# BattleBitsManual.net
KiCad netlist of a schematic drawn in EAGLE
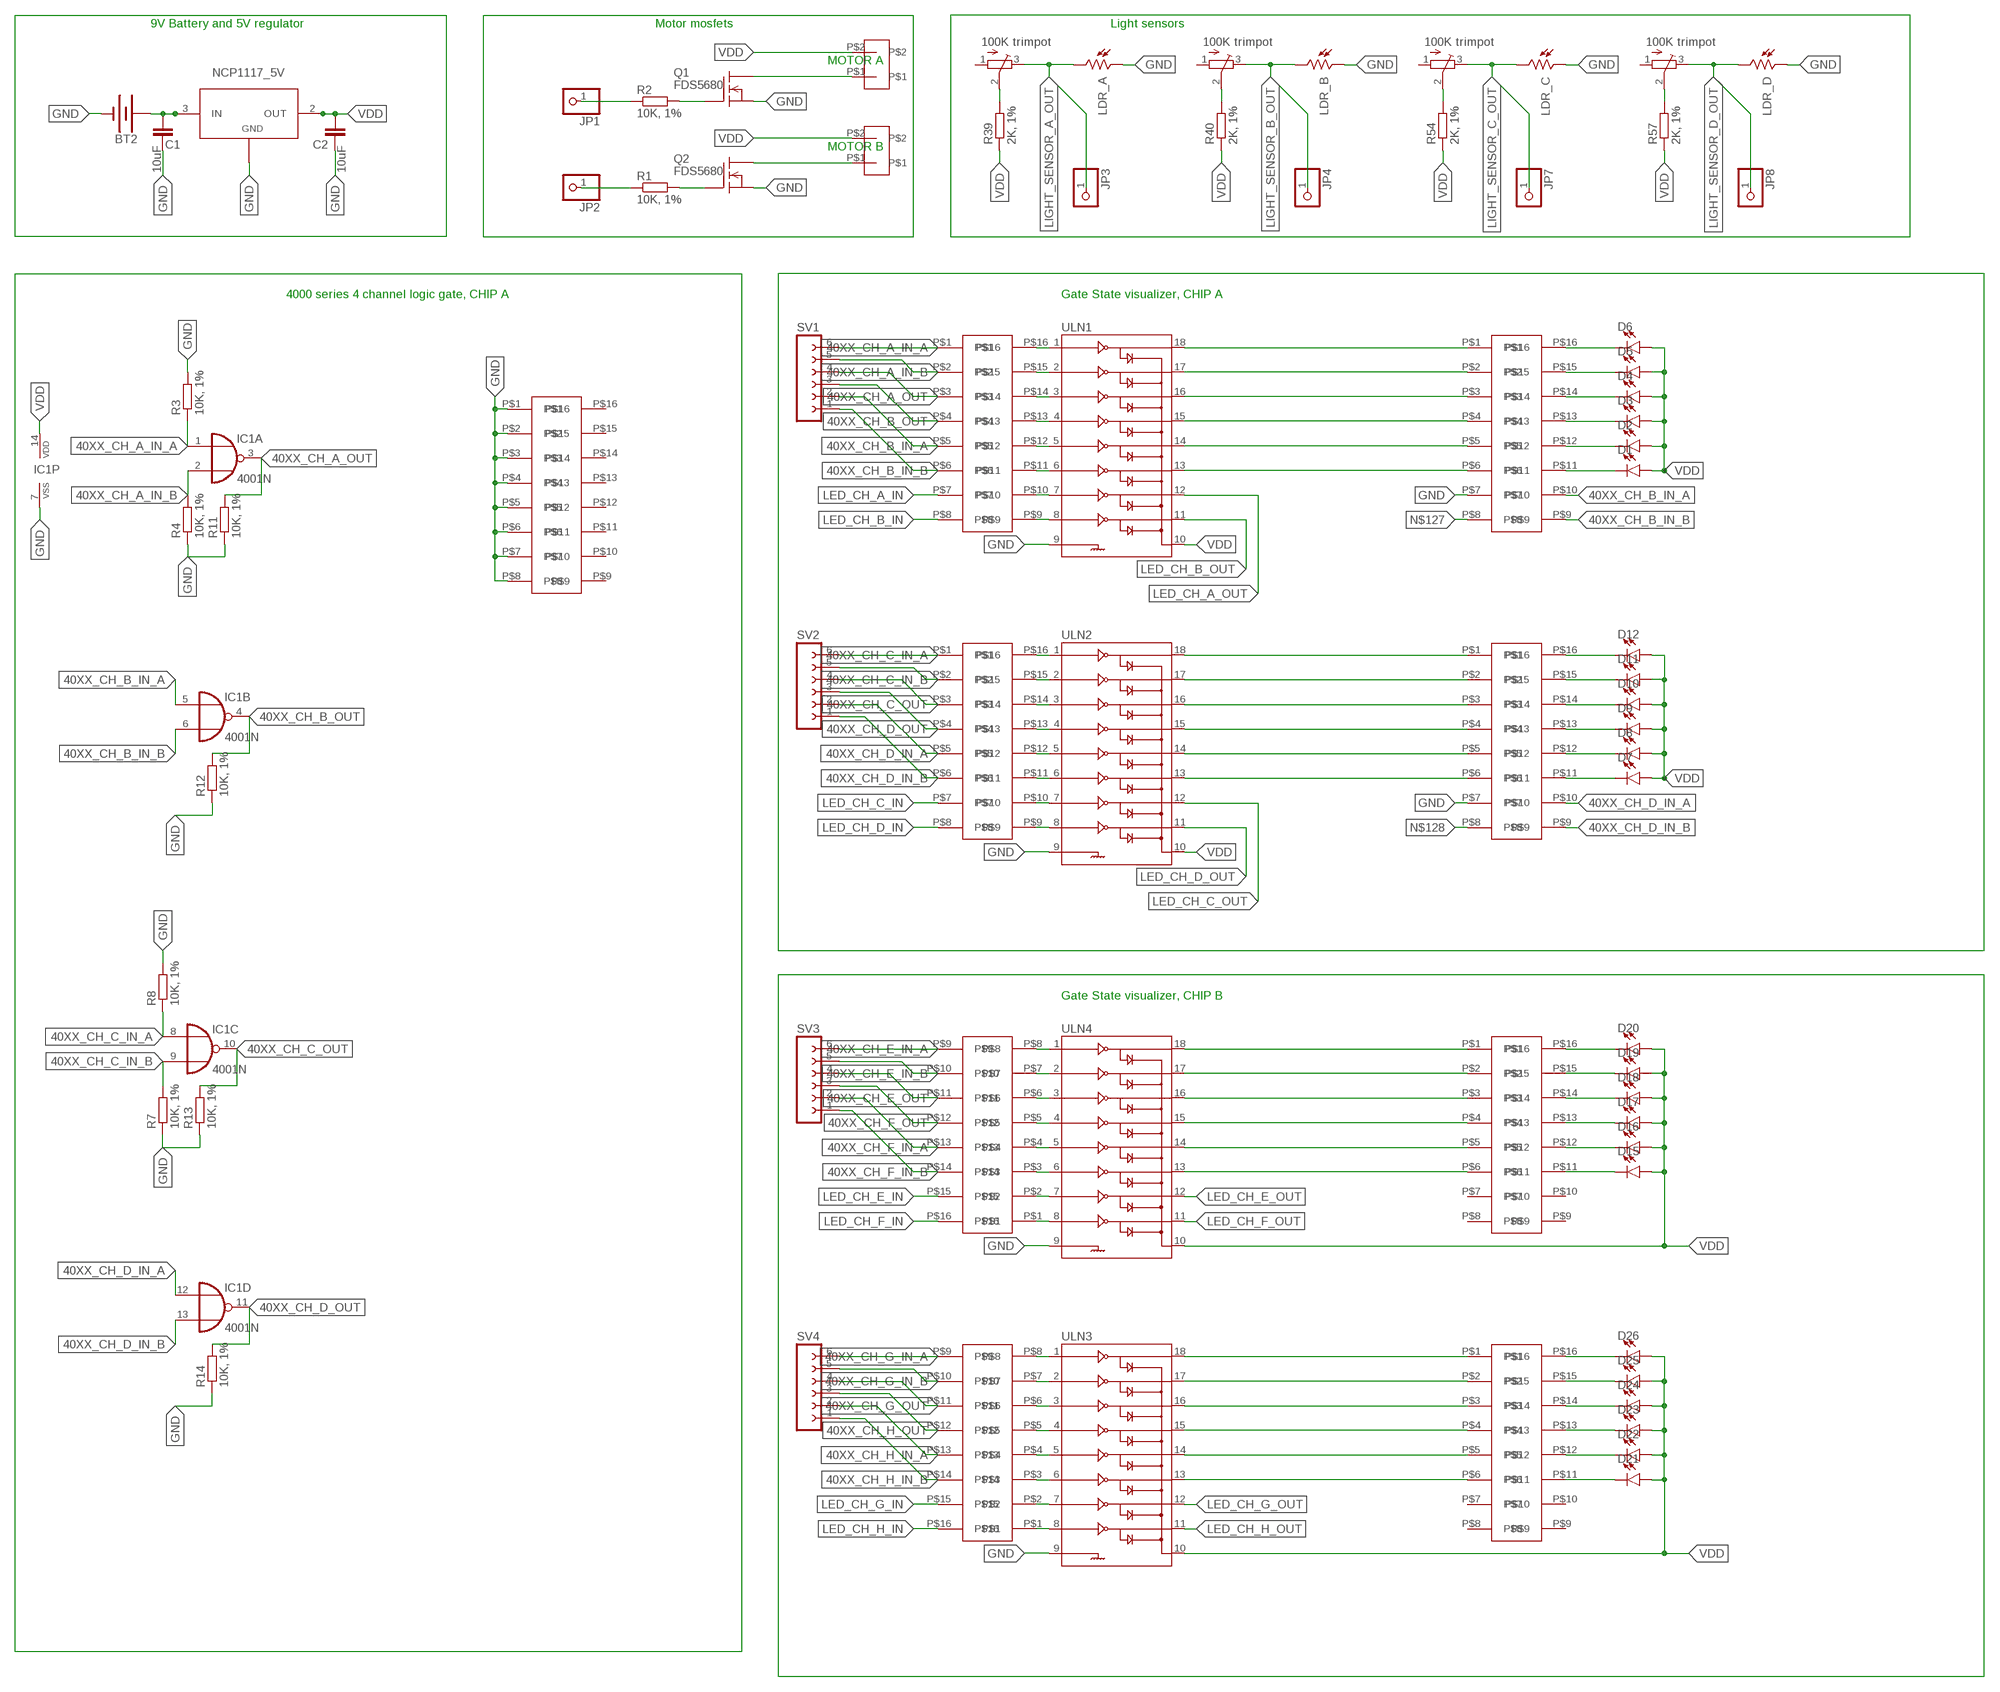
[diagram p0: schematic, sheet 1, part 1 of 3]
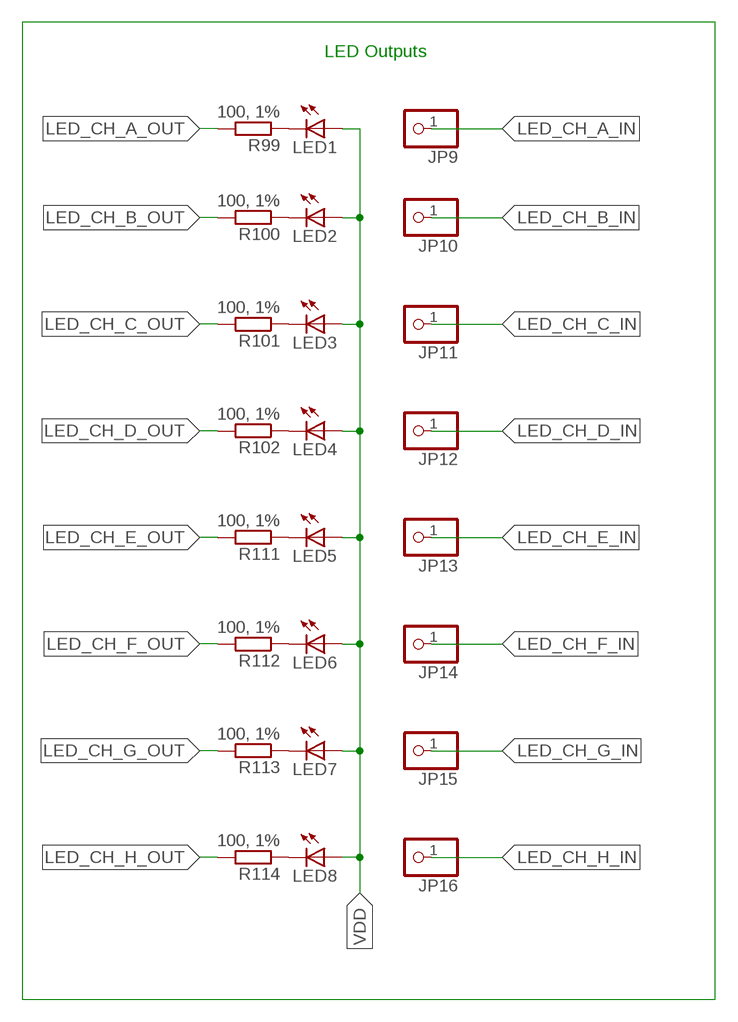
[diagram p1: schematic, sheet 1, part 2 of 3]
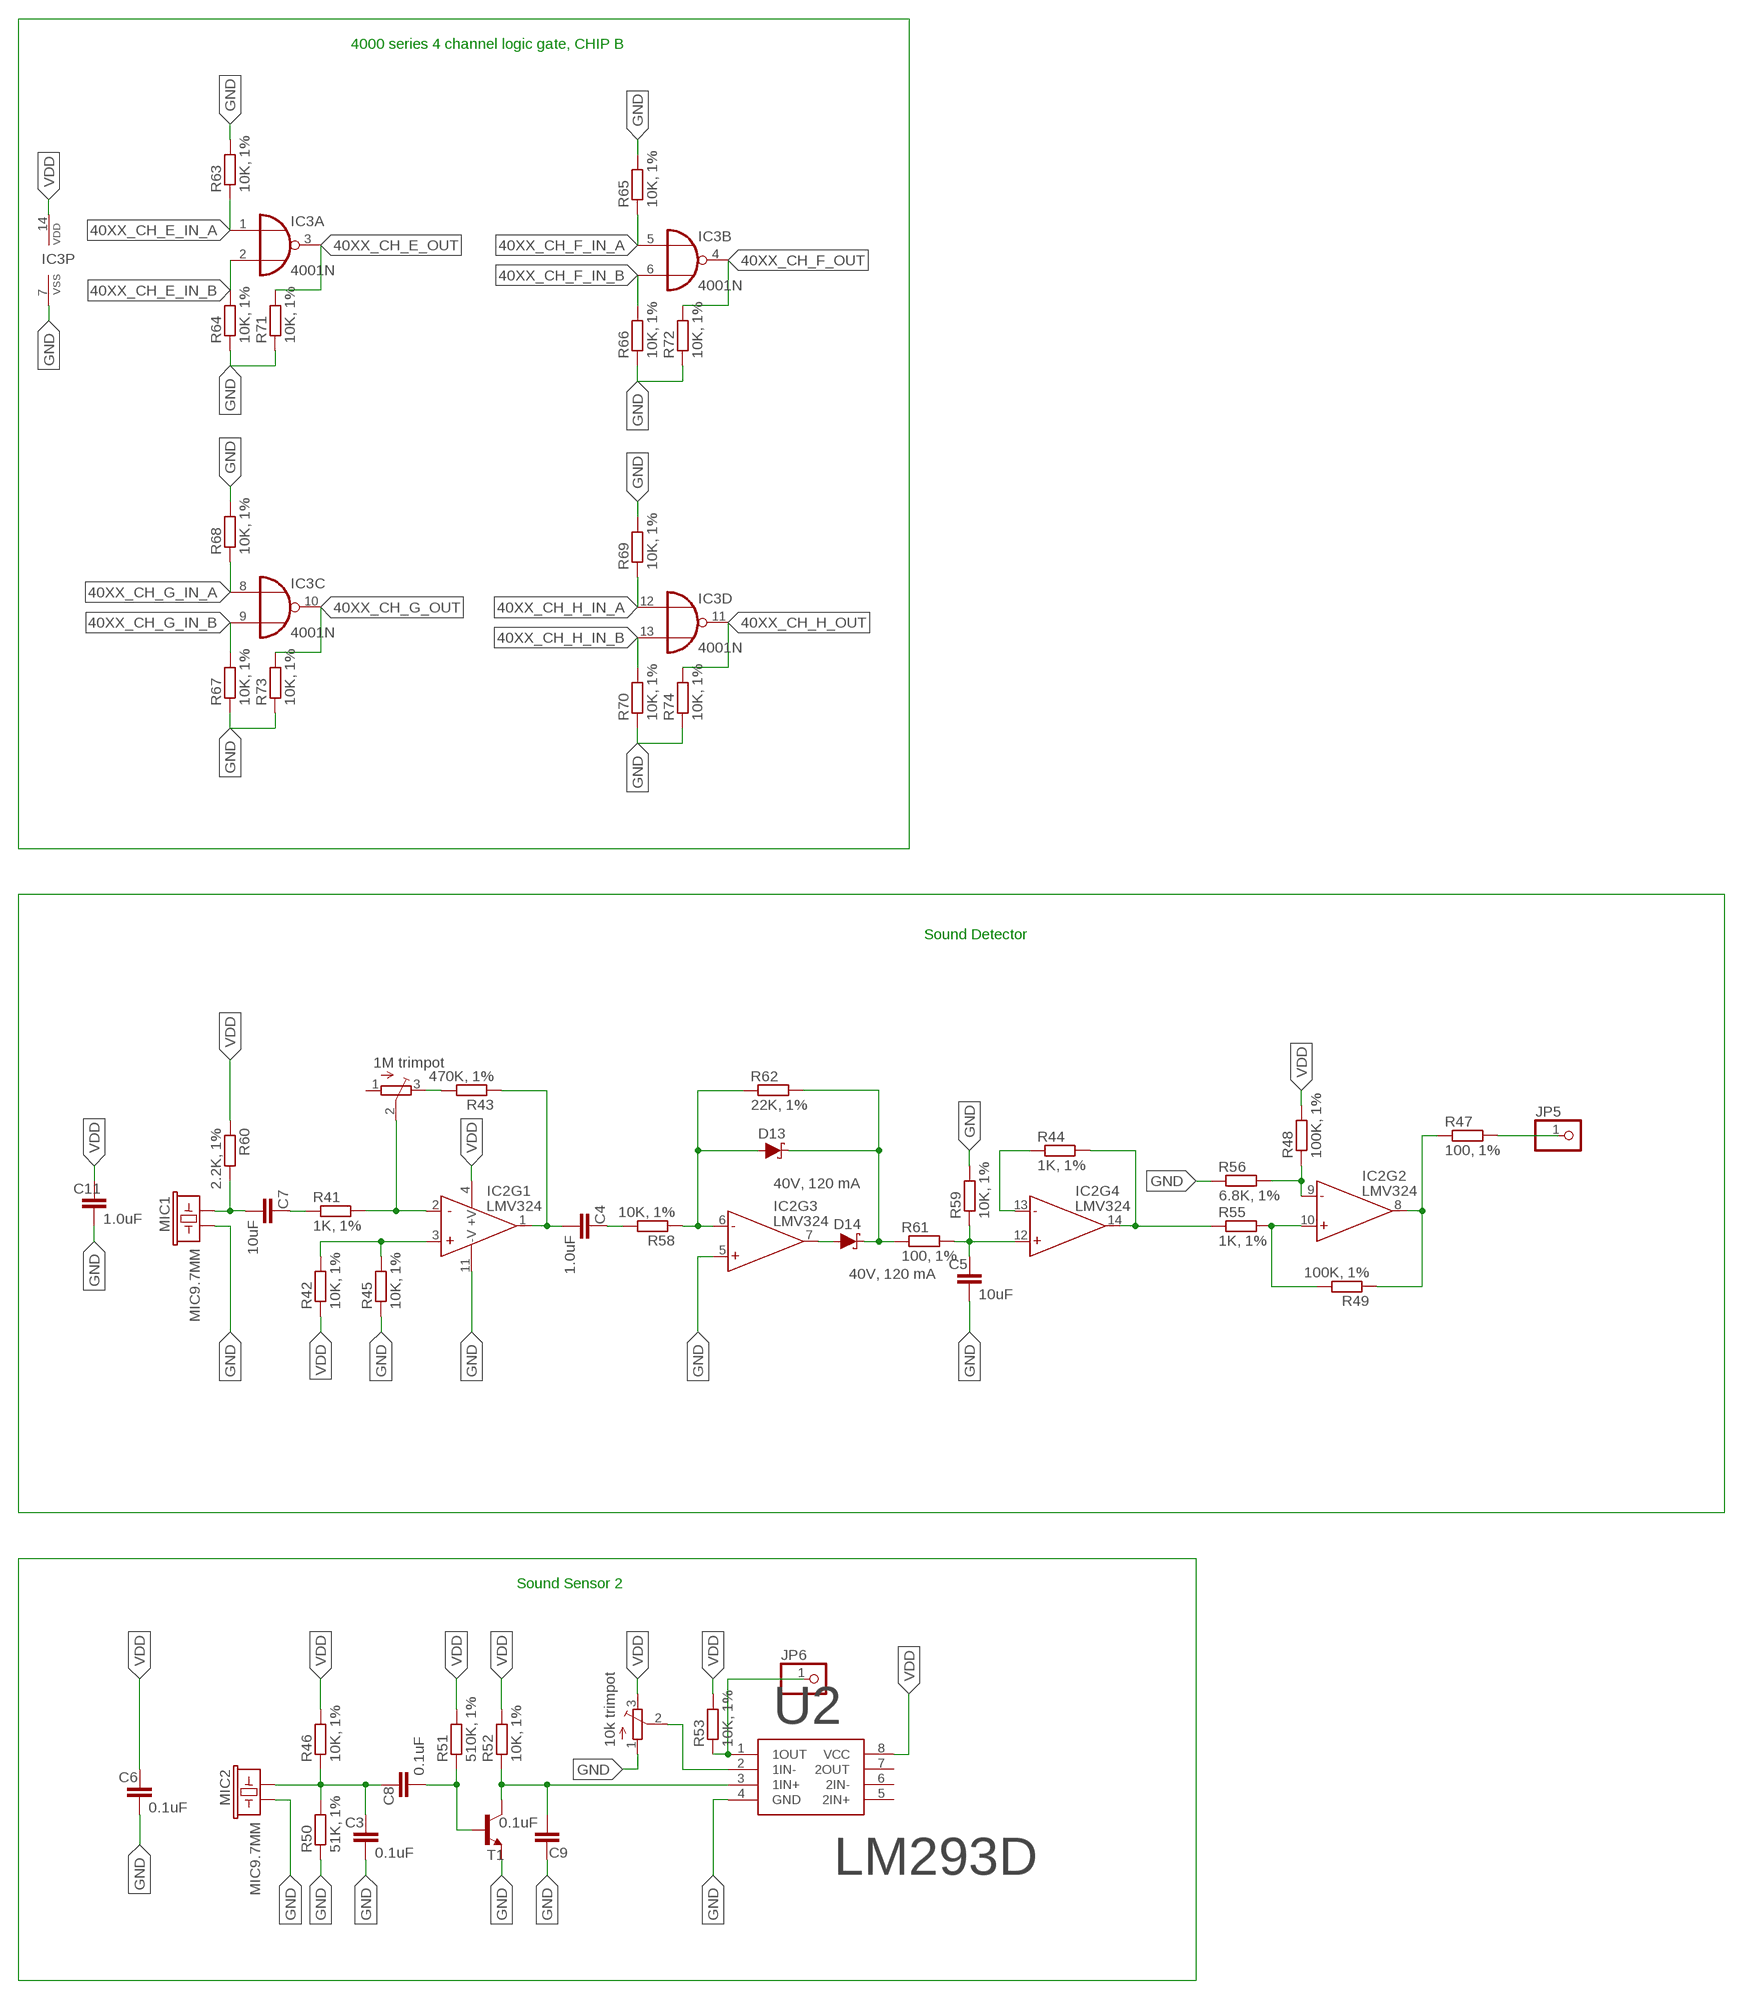
[diagram p2: schematic, sheet 1, part 3 of 3]

(export (version "E")
  (design (tool "Eeschema 10.0.6"))
  (components
    (comp (ref "BT2")
      (value "BATTERY-9V")
      (footprint "eagle-import:BATTCON_9V")
      (libsource (lib "eagle-import") (part "BATTERY-9V"))
    )
    (comp (ref "C1")
      (value "10uF")
      (footprint "eagle-import:C3216")
      (libsource (lib "eagle-import") (part "C-EUC3216"))
    )
    (comp (ref "C2")
      (value "10uF")
      (footprint "eagle-import:C3216")
      (libsource (lib "eagle-import") (part "C-EUC3216"))
    )
    (comp (ref "C3")
      (value "0.1uF")
      (footprint "eagle-import:C3216")
      (libsource (lib "eagle-import") (part "C-EUC3216"))
    )
    (comp (ref "C4")
      (value "1.0uF")
      (footprint "eagle-import:C3216")
      (libsource (lib "eagle-import") (part "C-EUC3216"))
    )
    (comp (ref "C5")
      (value "10uF")
      (footprint "eagle-import:C3216")
      (libsource (lib "eagle-import") (part "C-EUC3216"))
    )
    (comp (ref "C6")
      (value "0.1uF")
      (footprint "eagle-import:C3216")
      (libsource (lib "eagle-import") (part "C-EUC3216"))
    )
    (comp (ref "C7")
      (value "10uF")
      (footprint "eagle-import:C3216")
      (libsource (lib "eagle-import") (part "C-EUC3216"))
    )
    (comp (ref "C8")
      (value "0.1uF")
      (footprint "eagle-import:C3216")
      (libsource (lib "eagle-import") (part "C-EUC3216"))
    )
    (comp (ref "C9")
      (value "0.1uF")
      (footprint "eagle-import:C3216")
      (libsource (lib "eagle-import") (part "C-EUC3216"))
    )
    (comp (ref "C11")
      (value "1.0uF")
      (footprint "eagle-import:C3216")
      (libsource (lib "eagle-import") (part "C-EUC3216"))
    )
    (comp (ref "D1")
      (value "LED1206")
      (footprint "eagle-import:LED-1206")
      (libsource (lib "eagle-import") (part "LED1206"))
    )
    (comp (ref "D2")
      (value "LED1206")
      (footprint "eagle-import:LED-1206")
      (libsource (lib "eagle-import") (part "LED1206"))
    )
    (comp (ref "D3")
      (value "LED1206")
      (footprint "eagle-import:LED-1206")
      (libsource (lib "eagle-import") (part "LED1206"))
    )
    (comp (ref "D4")
      (value "LED1206")
      (footprint "eagle-import:LED-1206")
      (libsource (lib "eagle-import") (part "LED1206"))
    )
    (comp (ref "D5")
      (value "LED1206")
      (footprint "eagle-import:LED-1206")
      (libsource (lib "eagle-import") (part "LED1206"))
    )
    (comp (ref "D6")
      (value "LED1206")
      (footprint "eagle-import:LED-1206")
      (libsource (lib "eagle-import") (part "LED1206"))
    )
    (comp (ref "D7")
      (value "LED1206")
      (footprint "eagle-import:LED-1206")
      (libsource (lib "eagle-import") (part "LED1206"))
    )
    (comp (ref "D8")
      (value "LED1206")
      (footprint "eagle-import:LED-1206")
      (libsource (lib "eagle-import") (part "LED1206"))
    )
    (comp (ref "D9")
      (value "LED1206")
      (footprint "eagle-import:LED-1206")
      (libsource (lib "eagle-import") (part "LED1206"))
    )
    (comp (ref "D10")
      (value "LED1206")
      (footprint "eagle-import:LED-1206")
      (libsource (lib "eagle-import") (part "LED1206"))
    )
    (comp (ref "D11")
      (value "LED1206")
      (footprint "eagle-import:LED-1206")
      (libsource (lib "eagle-import") (part "LED1206"))
    )
    (comp (ref "D12")
      (value "LED1206")
      (footprint "eagle-import:LED-1206")
      (libsource (lib "eagle-import") (part "LED1206"))
    )
    (comp (ref "D13")
      (value "40V, 120 mA")
      (footprint "eagle-import:SOT23-3")
      (libsource (lib "eagle-import") (part "DIODE-SCHOTTKY-ZLLS500"))
    )
    (comp (ref "D14")
      (value "40V, 120 mA")
      (footprint "eagle-import:SOT23-3")
      (libsource (lib "eagle-import") (part "DIODE-SCHOTTKY-ZLLS500"))
    )
    (comp (ref "D15")
      (value "LED1206")
      (footprint "eagle-import:LED-1206")
      (libsource (lib "eagle-import") (part "LED1206"))
    )
    (comp (ref "D16")
      (value "LED1206")
      (footprint "eagle-import:LED-1206")
      (libsource (lib "eagle-import") (part "LED1206"))
    )
    (comp (ref "D17")
      (value "LED1206")
      (footprint "eagle-import:LED-1206")
      (libsource (lib "eagle-import") (part "LED1206"))
    )
    (comp (ref "D18")
      (value "LED1206")
      (footprint "eagle-import:LED-1206")
      (libsource (lib "eagle-import") (part "LED1206"))
    )
    (comp (ref "D19")
      (value "LED1206")
      (footprint "eagle-import:LED-1206")
      (libsource (lib "eagle-import") (part "LED1206"))
    )
    (comp (ref "D20")
      (value "LED1206")
      (footprint "eagle-import:LED-1206")
      (libsource (lib "eagle-import") (part "LED1206"))
    )
    (comp (ref "D21")
      (value "LED1206")
      (footprint "eagle-import:LED-1206")
      (libsource (lib "eagle-import") (part "LED1206"))
    )
    (comp (ref "D22")
      (value "LED1206")
      (footprint "eagle-import:LED-1206")
      (libsource (lib "eagle-import") (part "LED1206"))
    )
    (comp (ref "D23")
      (value "LED1206")
      (footprint "eagle-import:LED-1206")
      (libsource (lib "eagle-import") (part "LED1206"))
    )
    (comp (ref "D24")
      (value "LED1206")
      (footprint "eagle-import:LED-1206")
      (libsource (lib "eagle-import") (part "LED1206"))
    )
    (comp (ref "D25")
      (value "LED1206")
      (footprint "eagle-import:LED-1206")
      (libsource (lib "eagle-import") (part "LED1206"))
    )
    (comp (ref "D26")
      (value "LED1206")
      (footprint "eagle-import:LED-1206")
      (libsource (lib "eagle-import") (part "LED1206"))
    )
    (comp (ref "IC1")
      (value "4001N")
      (footprint "eagle-import:DIL14")
      (libsource (lib "eagle-import") (part "4001N"))
    )
    (comp (ref "IC2")
      (value "LMV324")
      (footprint "eagle-import:SO014")
      (libsource (lib "eagle-import") (part "LMV324"))
    )
    (comp (ref "IC3")
      (value "4001N")
      (footprint "eagle-import:DIL14")
      (libsource (lib "eagle-import") (part "4001N"))
    )
    (comp (ref "JP1")
      (value "PINHD-1X1")
      (footprint "eagle-import:1X01")
      (libsource (lib "eagle-import") (part "PINHD-1X1"))
    )
    (comp (ref "JP2")
      (value "PINHD-1X1")
      (footprint "eagle-import:1X01")
      (libsource (lib "eagle-import") (part "PINHD-1X1"))
    )
    (comp (ref "JP3")
      (value "PINHD-1X1")
      (footprint "eagle-import:1X01")
      (libsource (lib "eagle-import") (part "PINHD-1X1"))
    )
    (comp (ref "JP4")
      (value "PINHD-1X1")
      (footprint "eagle-import:1X01")
      (libsource (lib "eagle-import") (part "PINHD-1X1"))
    )
    (comp (ref "JP5")
      (value "PINHD-1X1")
      (footprint "eagle-import:1X01")
      (libsource (lib "eagle-import") (part "PINHD-1X1"))
    )
    (comp (ref "JP6")
      (value "PINHD-1X1")
      (footprint "eagle-import:1X01")
      (libsource (lib "eagle-import") (part "PINHD-1X1"))
    )
    (comp (ref "JP7")
      (value "PINHD-1X1")
      (footprint "eagle-import:1X01")
      (libsource (lib "eagle-import") (part "PINHD-1X1"))
    )
    (comp (ref "JP8")
      (value "PINHD-1X1")
      (footprint "eagle-import:1X01")
      (libsource (lib "eagle-import") (part "PINHD-1X1"))
    )
    (comp (ref "JP9")
      (value "PINHD-1X1")
      (footprint "eagle-import:1X01")
      (libsource (lib "eagle-import") (part "PINHD-1X1"))
    )
    (comp (ref "JP10")
      (value "PINHD-1X1")
      (footprint "eagle-import:1X01")
      (libsource (lib "eagle-import") (part "PINHD-1X1"))
    )
    (comp (ref "JP11")
      (value "PINHD-1X1")
      (footprint "eagle-import:1X01")
      (libsource (lib "eagle-import") (part "PINHD-1X1"))
    )
    (comp (ref "JP12")
      (value "PINHD-1X1")
      (footprint "eagle-import:1X01")
      (libsource (lib "eagle-import") (part "PINHD-1X1"))
    )
    (comp (ref "JP13")
      (value "PINHD-1X1")
      (footprint "eagle-import:1X01")
      (libsource (lib "eagle-import") (part "PINHD-1X1"))
    )
    (comp (ref "JP14")
      (value "PINHD-1X1")
      (footprint "eagle-import:1X01")
      (libsource (lib "eagle-import") (part "PINHD-1X1"))
    )
    (comp (ref "JP15")
      (value "PINHD-1X1")
      (footprint "eagle-import:1X01")
      (libsource (lib "eagle-import") (part "PINHD-1X1"))
    )
    (comp (ref "JP16")
      (value "PINHD-1X1")
      (footprint "eagle-import:1X01")
      (libsource (lib "eagle-import") (part "PINHD-1X1"))
    )
    (comp (ref "LDR_A")
      (value "V1060_21")
      (footprint "eagle-import:TO-5_V10")
      (libsource (lib "eagle-import") (part "?1060V_21"))
    )
    (comp (ref "LDR_B")
      (value "V1060_21")
      (footprint "eagle-import:TO-5_V10")
      (libsource (lib "eagle-import") (part "?1060V_21"))
    )
    (comp (ref "LDR_C")
      (value "V1060_21")
      (footprint "eagle-import:TO-5_V10")
      (libsource (lib "eagle-import") (part "?1060V_21"))
    )
    (comp (ref "LDR_D")
      (value "V1060_21")
      (footprint "eagle-import:TO-5_V10")
      (libsource (lib "eagle-import") (part "?1060V_21"))
    )
    (comp (ref "LED1")
      (value "LED5MM")
      (footprint "eagle-import:LED5MM")
      (libsource (lib "eagle-import") (part "adafruit_420_LED5MM"))
    )
    (comp (ref "LED2")
      (value "LED5MM")
      (footprint "eagle-import:LED5MM")
      (libsource (lib "eagle-import") (part "adafruit_420_LED5MM"))
    )
    (comp (ref "LED3")
      (value "LED5MM")
      (footprint "eagle-import:LED5MM")
      (libsource (lib "eagle-import") (part "adafruit_420_LED5MM"))
    )
    (comp (ref "LED4")
      (value "LED5MM")
      (footprint "eagle-import:LED5MM")
      (libsource (lib "eagle-import") (part "adafruit_420_LED5MM"))
    )
    (comp (ref "LED5")
      (value "LED5MM")
      (footprint "eagle-import:LED5MM")
      (libsource (lib "eagle-import") (part "adafruit_420_LED5MM"))
    )
    (comp (ref "LED6")
      (value "LED5MM")
      (footprint "eagle-import:LED5MM")
      (libsource (lib "eagle-import") (part "adafruit_420_LED5MM"))
    )
    (comp (ref "LED7")
      (value "LED5MM")
      (footprint "eagle-import:LED5MM")
      (libsource (lib "eagle-import") (part "adafruit_420_LED5MM"))
    )
    (comp (ref "LED8")
      (value "LED5MM")
      (footprint "eagle-import:LED5MM")
      (libsource (lib "eagle-import") (part "adafruit_420_LED5MM"))
    )
    (comp (ref "MIC1")
      (value "MIC9.7MM")
      (footprint "eagle-import:MIC-9.7MM")
      (libsource (lib "eagle-import") (part "MIC9.7MM"))
    )
    (comp (ref "MIC2")
      (value "MIC9.7MM")
      (footprint "eagle-import:MIC-9.7MM")
      (libsource (lib "eagle-import") (part "MIC9.7MM"))
    )
    (comp (ref "Q1")
      (value "FDS5680")
      (footprint "eagle-import:SO-8")
      (libsource (lib "eagle-import") (part "FDS5680"))
    )
    (comp (ref "Q2")
      (value "FDS5680")
      (footprint "eagle-import:SO-8")
      (libsource (lib "eagle-import") (part "FDS5680"))
    )
    (comp (ref "R1")
      (value "10K, 1%")
      (footprint "eagle-import:R3216")
      (libsource (lib "eagle-import") (part "R-EU_R3216"))
    )
    (comp (ref "R2")
      (value "10K, 1%")
      (footprint "eagle-import:R3216")
      (libsource (lib "eagle-import") (part "R-EU_R3216"))
    )
    (comp (ref "R3")
      (value "10K, 1%")
      (footprint "eagle-import:R3216")
      (libsource (lib "eagle-import") (part "R-EU_R3216"))
    )
    (comp (ref "R4")
      (value "10K, 1%")
      (footprint "eagle-import:R3216")
      (libsource (lib "eagle-import") (part "R-EU_R3216"))
    )
    (comp (ref "R7")
      (value "10K, 1%")
      (footprint "eagle-import:R3216")
      (libsource (lib "eagle-import") (part "R-EU_R3216"))
    )
    (comp (ref "R8")
      (value "10K, 1%")
      (footprint "eagle-import:R3216")
      (libsource (lib "eagle-import") (part "R-EU_R3216"))
    )
    (comp (ref "R11")
      (value "10K, 1%")
      (footprint "eagle-import:R3216")
      (libsource (lib "eagle-import") (part "R-EU_R3216"))
    )
    (comp (ref "R12")
      (value "10K, 1%")
      (footprint "eagle-import:R3216")
      (libsource (lib "eagle-import") (part "R-EU_R3216"))
    )
    (comp (ref "R13")
      (value "10K, 1%")
      (footprint "eagle-import:R3216")
      (libsource (lib "eagle-import") (part "R-EU_R3216"))
    )
    (comp (ref "R14")
      (value "10K, 1%")
      (footprint "eagle-import:R3216")
      (libsource (lib "eagle-import") (part "R-EU_R3216"))
    )
    (comp (ref "R39")
      (value "2K, 1%")
      (footprint "eagle-import:R3216")
      (libsource (lib "eagle-import") (part "R-EU_R3216"))
    )
    (comp (ref "R40")
      (value "2K, 1%")
      (footprint "eagle-import:R3216")
      (libsource (lib "eagle-import") (part "R-EU_R3216"))
    )
    (comp (ref "R41")
      (value "1K, 1%")
      (footprint "eagle-import:R3216")
      (libsource (lib "eagle-import") (part "R-EU_R3216"))
    )
    (comp (ref "R42")
      (value "10K, 1%")
      (footprint "eagle-import:R3216")
      (libsource (lib "eagle-import") (part "R-EU_R3216"))
    )
    (comp (ref "R43")
      (value "470K, 1%")
      (footprint "eagle-import:R3216")
      (libsource (lib "eagle-import") (part "R-EU_R3216"))
    )
    (comp (ref "R44")
      (value "1K, 1%")
      (footprint "eagle-import:R3216")
      (libsource (lib "eagle-import") (part "R-EU_R3216"))
    )
    (comp (ref "R45")
      (value "10K, 1%")
      (footprint "eagle-import:R3216")
      (libsource (lib "eagle-import") (part "R-EU_R3216"))
    )
    (comp (ref "R46")
      (value "10K, 1%")
      (footprint "eagle-import:R3216")
      (libsource (lib "eagle-import") (part "R-EU_R3216"))
    )
    (comp (ref "R47")
      (value "100, 1%")
      (footprint "eagle-import:R3216")
      (libsource (lib "eagle-import") (part "R-EU_R3216"))
    )
    (comp (ref "R48")
      (value "100K, 1%")
      (footprint "eagle-import:R3216")
      (libsource (lib "eagle-import") (part "R-EU_R3216"))
    )
    (comp (ref "R49")
      (value "100K, 1%")
      (footprint "eagle-import:R3216")
      (libsource (lib "eagle-import") (part "R-EU_R3216"))
    )
    (comp (ref "R50")
      (value "51K, 1%")
      (footprint "eagle-import:R3216")
      (libsource (lib "eagle-import") (part "R-EU_R3216"))
    )
    (comp (ref "R51")
      (value "510K, 1%")
      (footprint "eagle-import:R3216")
      (libsource (lib "eagle-import") (part "R-EU_R3216"))
    )
    (comp (ref "R52")
      (value "10K, 1%")
      (footprint "eagle-import:R3216")
      (libsource (lib "eagle-import") (part "R-EU_R3216"))
    )
    (comp (ref "R53")
      (value "10K, 1%")
      (footprint "eagle-import:R3216")
      (libsource (lib "eagle-import") (part "R-EU_R3216"))
    )
    (comp (ref "R54")
      (value "2K, 1%")
      (footprint "eagle-import:R3216")
      (libsource (lib "eagle-import") (part "R-EU_R3216"))
    )
    (comp (ref "R55")
      (value "1K, 1%")
      (footprint "eagle-import:R3216")
      (libsource (lib "eagle-import") (part "R-EU_R3216"))
    )
    (comp (ref "R56")
      (value "6.8K, 1%")
      (footprint "eagle-import:R3216")
      (libsource (lib "eagle-import") (part "R-EU_R3216"))
    )
    (comp (ref "R57")
      (value "2K, 1%")
      (footprint "eagle-import:R3216")
      (libsource (lib "eagle-import") (part "R-EU_R3216"))
    )
    (comp (ref "R58")
      (value "10K, 1%")
      (footprint "eagle-import:R3216")
      (libsource (lib "eagle-import") (part "R-EU_R3216"))
    )
    (comp (ref "R59")
      (value "10K, 1%")
      (footprint "eagle-import:R3216")
      (libsource (lib "eagle-import") (part "R-EU_R3216"))
    )
    (comp (ref "R60")
      (value "2.2K, 1%")
      (footprint "eagle-import:R3216")
      (libsource (lib "eagle-import") (part "R-EU_R3216"))
    )
    (comp (ref "R61")
      (value "100, 1%")
      (footprint "eagle-import:R3216")
      (libsource (lib "eagle-import") (part "R-EU_R3216"))
    )
    (comp (ref "R62")
      (value "22K, 1%")
      (footprint "eagle-import:R3216")
      (libsource (lib "eagle-import") (part "R-EU_R3216"))
    )
    (comp (ref "R63")
      (value "10K, 1%")
      (footprint "eagle-import:R3216")
      (libsource (lib "eagle-import") (part "R-EU_R3216"))
    )
    (comp (ref "R64")
      (value "10K, 1%")
      (footprint "eagle-import:R3216")
      (libsource (lib "eagle-import") (part "R-EU_R3216"))
    )
    (comp (ref "R65")
      (value "10K, 1%")
      (footprint "eagle-import:R3216")
      (libsource (lib "eagle-import") (part "R-EU_R3216"))
    )
    (comp (ref "R66")
      (value "10K, 1%")
      (footprint "eagle-import:R3216")
      (libsource (lib "eagle-import") (part "R-EU_R3216"))
    )
    (comp (ref "R67")
      (value "10K, 1%")
      (footprint "eagle-import:R3216")
      (libsource (lib "eagle-import") (part "R-EU_R3216"))
    )
    (comp (ref "R68")
      (value "10K, 1%")
      (footprint "eagle-import:R3216")
      (libsource (lib "eagle-import") (part "R-EU_R3216"))
    )
    (comp (ref "R69")
      (value "10K, 1%")
      (footprint "eagle-import:R3216")
      (libsource (lib "eagle-import") (part "R-EU_R3216"))
    )
    (comp (ref "R70")
      (value "10K, 1%")
      (footprint "eagle-import:R3216")
      (libsource (lib "eagle-import") (part "R-EU_R3216"))
    )
    (comp (ref "R71")
      (value "10K, 1%")
      (footprint "eagle-import:R3216")
      (libsource (lib "eagle-import") (part "R-EU_R3216"))
    )
    (comp (ref "R72")
      (value "10K, 1%")
      (footprint "eagle-import:R3216")
      (libsource (lib "eagle-import") (part "R-EU_R3216"))
    )
    (comp (ref "R73")
      (value "10K, 1%")
      (footprint "eagle-import:R3216")
      (libsource (lib "eagle-import") (part "R-EU_R3216"))
    )
    (comp (ref "R74")
      (value "10K, 1%")
      (footprint "eagle-import:R3216")
      (libsource (lib "eagle-import") (part "R-EU_R3216"))
    )
    (comp (ref "R99")
      (value "100, 1%")
      (footprint "eagle-import:R3216")
      (libsource (lib "eagle-import") (part "R-EU_R3216"))
    )
    (comp (ref "R100")
      (value "100, 1%")
      (footprint "eagle-import:R3216")
      (libsource (lib "eagle-import") (part "R-EU_R3216"))
    )
    (comp (ref "R101")
      (value "100, 1%")
      (footprint "eagle-import:R3216")
      (libsource (lib "eagle-import") (part "R-EU_R3216"))
    )
    (comp (ref "R102")
      (value "100, 1%")
      (footprint "eagle-import:R3216")
      (libsource (lib "eagle-import") (part "R-EU_R3216"))
    )
    (comp (ref "R111")
      (value "100, 1%")
      (footprint "eagle-import:R3216")
      (libsource (lib "eagle-import") (part "R-EU_R3216"))
    )
    (comp (ref "R112")
      (value "100, 1%")
      (footprint "eagle-import:R3216")
      (libsource (lib "eagle-import") (part "R-EU_R3216"))
    )
    (comp (ref "R113")
      (value "100, 1%")
      (footprint "eagle-import:R3216")
      (libsource (lib "eagle-import") (part "R-EU_R3216"))
    )
    (comp (ref "R114")
      (value "100, 1%")
      (footprint "eagle-import:R3216")
      (libsource (lib "eagle-import") (part "R-EU_R3216"))
    )
    (comp (ref "SV1")
      (value "FE06-1")
      (footprint "eagle-import:FE06")
      (libsource (lib "eagle-import") (part "FE06-1"))
    )
    (comp (ref "SV2")
      (value "FE06-1")
      (footprint "eagle-import:FE06")
      (libsource (lib "eagle-import") (part "FE06-1"))
    )
    (comp (ref "SV3")
      (value "FE06-1")
      (footprint "eagle-import:FE06")
      (libsource (lib "eagle-import") (part "FE06-1"))
    )
    (comp (ref "SV4")
      (value "FE06-1")
      (footprint "eagle-import:FE06")
      (libsource (lib "eagle-import") (part "FE06-1"))
    )
    (comp (ref "T1")
      (value "BC808-NPN-SOT23-BEC")
      (footprint "eagle-import:SOT23-BEC")
      (libsource (lib "eagle-import") (part "-NPN-SOT23-BECBC808"))
    )
    (comp (ref "TM1")
      (value "100K trimpot")
      (footprint "eagle-import:TC33X")
      (libsource (lib "eagle-import") (part "TRIMPOTTC33X"))
    )
    (comp (ref "TM2")
      (value "100K trimpot")
      (footprint "eagle-import:TC33X")
      (libsource (lib "eagle-import") (part "TRIMPOTTC33X"))
    )
    (comp (ref "TM3")
      (value "1M trimpot")
      (footprint "eagle-import:TC33X")
      (libsource (lib "eagle-import") (part "TRIMPOTTC33X"))
    )
    (comp (ref "TM4")
      (value "10k trimpot")
      (footprint "eagle-import:TC33X")
      (libsource (lib "eagle-import") (part "TRIMPOTTC33X"))
    )
    (comp (ref "TM5")
      (value "100K trimpot")
      (footprint "eagle-import:TC33X")
      (libsource (lib "eagle-import") (part "TRIMPOTTC33X"))
    )
    (comp (ref "TM6")
      (value "100K trimpot")
      (footprint "eagle-import:TC33X")
      (libsource (lib "eagle-import") (part "TRIMPOTTC33X"))
    )
    (comp (ref "U$1")
      (value "MOTOR")
      (footprint "eagle-import:GEARMOTOR")
      (libsource (lib "eagle-import") (part "MOTOR"))
    )
    (comp (ref "U$2")
      (value "MOTOR")
      (footprint "eagle-import:GEARMOTOR")
      (libsource (lib "eagle-import") (part "MOTOR"))
    )
    (comp (ref "U$3")
      (value "8_RES_ISO_SOIC16")
      (footprint "eagle-import:8_RES_ISO_SOIC16")
      (libsource (lib "eagle-import") (part "8_RES_ISO_SOIC16"))
    )
    (comp (ref "U$4")
      (value "8_RES_ISO_SOIC16")
      (footprint "eagle-import:8_RES_ISO_SOIC16")
      (libsource (lib "eagle-import") (part "8_RES_ISO_SOIC16"))
    )
    (comp (ref "U$5")
      (value "8_RES_ISO_SOIC16")
      (footprint "eagle-import:8_RES_ISO_SOIC16")
      (libsource (lib "eagle-import") (part "8_RES_ISO_SOIC16"))
    )
    (comp (ref "U$6")
      (value "8_RES_ISO_SOIC16")
      (footprint "eagle-import:8_RES_ISO_SOIC16")
      (libsource (lib "eagle-import") (part "8_RES_ISO_SOIC16"))
    )
    (comp (ref "U$7")
      (value "8_RES_ISO_SOIC16")
      (footprint "eagle-import:8_RES_ISO_SOIC16")
      (libsource (lib "eagle-import") (part "8_RES_ISO_SOIC16"))
    )
    (comp (ref "U$8")
      (value "8_RES_ISO_SOIC16")
      (footprint "eagle-import:8_RES_ISO_SOIC16")
      (libsource (lib "eagle-import") (part "8_RES_ISO_SOIC16"))
    )
    (comp (ref "U$9")
      (value "8_RES_ISO_SOIC16")
      (footprint "eagle-import:8_RES_ISO_SOIC16")
      (libsource (lib "eagle-import") (part "8_RES_ISO_SOIC16"))
    )
    (comp (ref "U$10")
      (value "8_RES_ISO_SOIC16")
      (footprint "eagle-import:8_RES_ISO_SOIC16")
      (libsource (lib "eagle-import") (part "8_RES_ISO_SOIC16"))
    )
    (comp (ref "U$11")
      (value "8_RES_ISO_SOIC16")
      (footprint "eagle-import:8_RES_ISO_SOIC16")
      (libsource (lib "eagle-import") (part "8_RES_ISO_SOIC16"))
    )
    (comp (ref "U1")
      (value "NCP1117_5V")
      (footprint "eagle-import:SOT-223")
      (fields
        (field (name "DIGIKEY_PART_NUMBER") "NCP1117ST33T3GOSTR-ND")
        (field (name "MANUFACTURER") "ON Semiconductor")
        (field (name "MPN") "NCP1117ST33T3G")
        (field (name "CREATED_BY") "PCBLayout.com")
      )
      (libsource (lib "eagle-import") (part "NCP1117ST33T3G"))
    )
    (comp (ref "U2")
      (value "LM293D")
      (footprint "eagle-import:8-SOIC")
      (fields
        (field (name "DIGIKEY_PART_NUMBER") "296-9531-5-ND")
        (field (name "MANUFACTURER") "Texas Instruments")
        (field (name "CREATED_BY") "PCBLayout.com")
      )
      (libsource (lib "eagle-import") (part "LM293D"))
    )
    (comp (ref "ULN1")
      (value "ULN2803SOICW")
      (footprint "eagle-import:SO18L")
      (libsource (lib "eagle-import") (part "ULN2803SOICW"))
    )
    (comp (ref "ULN2")
      (value "ULN2803SOICW")
      (footprint "eagle-import:SO18L")
      (libsource (lib "eagle-import") (part "ULN2803SOICW"))
    )
    (comp (ref "ULN3")
      (value "ULN2803SOICW")
      (footprint "eagle-import:SO18L")
      (libsource (lib "eagle-import") (part "ULN2803SOICW"))
    )
    (comp (ref "ULN4")
      (value "ULN2803SOICW")
      (footprint "eagle-import:SO18L")
      (libsource (lib "eagle-import") (part "ULN2803SOICW"))
    )
  )
  (nets
    (net (code "1") (name "40XX_CH_A_IN_A") (class "Default")
      (node (ref "IC1") (pin "1") (pinfunction "I0_1") (pintype "input"))
      (node (ref "R3") (pin "1") (pinfunction "1_1") (pintype "passive"))
      (node (ref "SV1") (pin "6") (pinfunction "6_6") (pintype "passive"))
      (node (ref "U$9") (pin "P$1") (pinfunction "P$1_P$1") (pintype "bidirectional"))
    )
    (net (code "2") (name "40XX_CH_A_IN_B") (class "Default")
      (node (ref "IC1") (pin "2") (pinfunction "I1_2") (pintype "input"))
      (node (ref "R4") (pin "2") (pinfunction "2_2") (pintype "passive"))
      (node (ref "SV1") (pin "5") (pinfunction "5_5") (pintype "passive"))
      (node (ref "U$9") (pin "P$2") (pinfunction "P$2_P$2") (pintype "bidirectional"))
    )
    (net (code "3") (name "40XX_CH_A_OUT") (class "Default")
      (node (ref "IC1") (pin "3") (pinfunction "O_3") (pintype "output"))
      (node (ref "R11") (pin "2") (pinfunction "2_2") (pintype "passive"))
      (node (ref "SV1") (pin "4") (pinfunction "4_4") (pintype "passive"))
      (node (ref "U$9") (pin "P$3") (pinfunction "P$3_P$3") (pintype "bidirectional"))
    )
    (net (code "4") (name "40XX_CH_B_IN_A") (class "Default")
      (node (ref "IC1") (pin "5") (pinfunction "I0_5") (pintype "input"))
      (node (ref "SV1") (pin "2") (pinfunction "2_2") (pintype "passive"))
      (node (ref "U$3") (pin "P$10") (pinfunction "P$10_P$10") (pintype "bidirectional"))
      (node (ref "U$9") (pin "P$5") (pinfunction "P$5_P$5") (pintype "bidirectional"))
    )
    (net (code "5") (name "40XX_CH_B_IN_B") (class "Default")
      (node (ref "IC1") (pin "6") (pinfunction "I1_6") (pintype "input"))
      (node (ref "SV1") (pin "1") (pinfunction "1_1") (pintype "passive"))
      (node (ref "U$3") (pin "P$9") (pinfunction "P$9_P$9") (pintype "bidirectional"))
      (node (ref "U$9") (pin "P$6") (pinfunction "P$6_P$6") (pintype "bidirectional"))
    )
    (net (code "6") (name "40XX_CH_B_OUT") (class "Default")
      (node (ref "IC1") (pin "4") (pinfunction "O_4") (pintype "output"))
      (node (ref "R12") (pin "2") (pinfunction "2_2") (pintype "passive"))
      (node (ref "SV1") (pin "3") (pinfunction "3_3") (pintype "passive"))
      (node (ref "U$9") (pin "P$4") (pinfunction "P$4_P$4") (pintype "bidirectional"))
    )
    (net (code "7") (name "40XX_CH_C_IN_A") (class "Default")
      (node (ref "IC1") (pin "8") (pinfunction "I0_8") (pintype "input"))
      (node (ref "R8") (pin "1") (pinfunction "1_1") (pintype "passive"))
      (node (ref "SV2") (pin "6") (pinfunction "6_6") (pintype "passive"))
      (node (ref "U$4") (pin "P$1") (pinfunction "P$1_P$1") (pintype "bidirectional"))
    )
    (net (code "8") (name "40XX_CH_C_IN_B") (class "Default")
      (node (ref "IC1") (pin "9") (pinfunction "I1_9") (pintype "input"))
      (node (ref "R7") (pin "2") (pinfunction "2_2") (pintype "passive"))
      (node (ref "SV2") (pin "5") (pinfunction "5_5") (pintype "passive"))
      (node (ref "U$4") (pin "P$2") (pinfunction "P$2_P$2") (pintype "bidirectional"))
    )
    (net (code "9") (name "40XX_CH_C_OUT") (class "Default")
      (node (ref "IC1") (pin "10") (pinfunction "O_10") (pintype "output"))
      (node (ref "R13") (pin "2") (pinfunction "2_2") (pintype "passive"))
      (node (ref "SV2") (pin "4") (pinfunction "4_4") (pintype "passive"))
      (node (ref "U$4") (pin "P$3") (pinfunction "P$3_P$3") (pintype "bidirectional"))
    )
    (net (code "10") (name "40XX_CH_D_IN_A") (class "Default")
      (node (ref "IC1") (pin "12") (pinfunction "I0_12") (pintype "input"))
      (node (ref "SV2") (pin "2") (pinfunction "2_2") (pintype "passive"))
      (node (ref "U$4") (pin "P$5") (pinfunction "P$5_P$5") (pintype "bidirectional"))
      (node (ref "U$7") (pin "P$10") (pinfunction "P$10_P$10") (pintype "bidirectional"))
    )
    (net (code "11") (name "40XX_CH_D_IN_B") (class "Default")
      (node (ref "IC1") (pin "13") (pinfunction "I1_13") (pintype "input"))
      (node (ref "SV2") (pin "1") (pinfunction "1_1") (pintype "passive"))
      (node (ref "U$4") (pin "P$6") (pinfunction "P$6_P$6") (pintype "bidirectional"))
      (node (ref "U$7") (pin "P$9") (pinfunction "P$9_P$9") (pintype "bidirectional"))
    )
    (net (code "12") (name "40XX_CH_D_OUT") (class "Default")
      (node (ref "IC1") (pin "11") (pinfunction "O_11") (pintype "output"))
      (node (ref "R14") (pin "2") (pinfunction "2_2") (pintype "passive"))
      (node (ref "SV2") (pin "3") (pinfunction "3_3") (pintype "passive"))
      (node (ref "U$4") (pin "P$4") (pinfunction "P$4_P$4") (pintype "bidirectional"))
    )
    (net (code "13") (name "40XX_CH_E_IN_A") (class "Default")
      (node (ref "IC3") (pin "1") (pinfunction "I0_1") (pintype "input"))
      (node (ref "R63") (pin "1") (pinfunction "1_1") (pintype "passive"))
      (node (ref "SV3") (pin "6") (pinfunction "6_6") (pintype "passive"))
      (node (ref "U$5") (pin "P$9") (pinfunction "P$9_P$9") (pintype "bidirectional"))
    )
    (net (code "14") (name "40XX_CH_E_IN_B") (class "Default")
      (node (ref "IC3") (pin "2") (pinfunction "I1_2") (pintype "input"))
      (node (ref "R64") (pin "2") (pinfunction "2_2") (pintype "passive"))
      (node (ref "SV3") (pin "5") (pinfunction "5_5") (pintype "passive"))
      (node (ref "U$5") (pin "P$10") (pinfunction "P$10_P$10") (pintype "bidirectional"))
    )
    (net (code "15") (name "40XX_CH_E_OUT") (class "Default")
      (node (ref "IC3") (pin "3") (pinfunction "O_3") (pintype "output"))
      (node (ref "R71") (pin "2") (pinfunction "2_2") (pintype "passive"))
      (node (ref "SV3") (pin "4") (pinfunction "4_4") (pintype "passive"))
      (node (ref "U$5") (pin "P$11") (pinfunction "P$11_P$11") (pintype "bidirectional"))
    )
    (net (code "16") (name "40XX_CH_F_IN_A") (class "Default")
      (node (ref "IC3") (pin "5") (pinfunction "I0_5") (pintype "input"))
      (node (ref "R65") (pin "1") (pinfunction "1_1") (pintype "passive"))
      (node (ref "SV3") (pin "2") (pinfunction "2_2") (pintype "passive"))
      (node (ref "U$5") (pin "P$13") (pinfunction "P$13_P$13") (pintype "bidirectional"))
    )
    (net (code "17") (name "40XX_CH_F_IN_B") (class "Default")
      (node (ref "IC3") (pin "6") (pinfunction "I1_6") (pintype "input"))
      (node (ref "R66") (pin "2") (pinfunction "2_2") (pintype "passive"))
      (node (ref "SV3") (pin "1") (pinfunction "1_1") (pintype "passive"))
      (node (ref "U$5") (pin "P$14") (pinfunction "P$14_P$14") (pintype "bidirectional"))
    )
    (net (code "18") (name "40XX_CH_F_OUT") (class "Default")
      (node (ref "IC3") (pin "4") (pinfunction "O_4") (pintype "output"))
      (node (ref "R72") (pin "2") (pinfunction "2_2") (pintype "passive"))
      (node (ref "SV3") (pin "3") (pinfunction "3_3") (pintype "passive"))
      (node (ref "U$5") (pin "P$12") (pinfunction "P$12_P$12") (pintype "bidirectional"))
    )
    (net (code "19") (name "40XX_CH_G_IN_A") (class "Default")
      (node (ref "IC3") (pin "8") (pinfunction "I0_8") (pintype "input"))
      (node (ref "R68") (pin "1") (pinfunction "1_1") (pintype "passive"))
      (node (ref "SV4") (pin "6") (pinfunction "6_6") (pintype "passive"))
      (node (ref "U$6") (pin "P$9") (pinfunction "P$9_P$9") (pintype "bidirectional"))
    )
    (net (code "20") (name "40XX_CH_G_IN_B") (class "Default")
      (node (ref "IC3") (pin "9") (pinfunction "I1_9") (pintype "input"))
      (node (ref "R67") (pin "2") (pinfunction "2_2") (pintype "passive"))
      (node (ref "SV4") (pin "5") (pinfunction "5_5") (pintype "passive"))
      (node (ref "U$6") (pin "P$10") (pinfunction "P$10_P$10") (pintype "bidirectional"))
    )
    (net (code "21") (name "40XX_CH_G_OUT") (class "Default")
      (node (ref "IC3") (pin "10") (pinfunction "O_10") (pintype "output"))
      (node (ref "R73") (pin "2") (pinfunction "2_2") (pintype "passive"))
      (node (ref "SV4") (pin "4") (pinfunction "4_4") (pintype "passive"))
      (node (ref "U$6") (pin "P$11") (pinfunction "P$11_P$11") (pintype "bidirectional"))
    )
    (net (code "22") (name "40XX_CH_H_IN_A") (class "Default")
      (node (ref "IC3") (pin "12") (pinfunction "I0_12") (pintype "input"))
      (node (ref "R69") (pin "1") (pinfunction "1_1") (pintype "passive"))
      (node (ref "SV4") (pin "2") (pinfunction "2_2") (pintype "passive"))
      (node (ref "U$6") (pin "P$13") (pinfunction "P$13_P$13") (pintype "bidirectional"))
    )
    (net (code "23") (name "40XX_CH_H_IN_B") (class "Default")
      (node (ref "IC3") (pin "13") (pinfunction "I1_13") (pintype "input"))
      (node (ref "R70") (pin "2") (pinfunction "2_2") (pintype "passive"))
      (node (ref "SV4") (pin "1") (pinfunction "1_1") (pintype "passive"))
      (node (ref "U$6") (pin "P$14") (pinfunction "P$14_P$14") (pintype "bidirectional"))
    )
    (net (code "24") (name "40XX_CH_H_OUT") (class "Default")
      (node (ref "IC3") (pin "11") (pinfunction "O_11") (pintype "output"))
      (node (ref "R74") (pin "2") (pinfunction "2_2") (pintype "passive"))
      (node (ref "SV4") (pin "3") (pinfunction "3_3") (pintype "passive"))
      (node (ref "U$6") (pin "P$12") (pinfunction "P$12_P$12") (pintype "bidirectional"))
    )
    (net (code "25") (name "GND") (class "Default")
      (node (ref "BT2") (pin "-") (pinfunction "-_-") (pintype "power_in"))
      (node (ref "C1") (pin "1") (pinfunction "1_1") (pintype "passive"))
      (node (ref "C11") (pin "2") (pinfunction "2_2") (pintype "passive"))
      (node (ref "C2") (pin "1") (pinfunction "1_1") (pintype "passive"))
      (node (ref "C3") (pin "2") (pinfunction "2_2") (pintype "passive"))
      (node (ref "C5") (pin "2") (pinfunction "2_2") (pintype "passive"))
      (node (ref "C6") (pin "2") (pinfunction "2_2") (pintype "passive"))
      (node (ref "C9") (pin "1") (pinfunction "1_1") (pintype "passive"))
      (node (ref "IC1") (pin "7") (pinfunction "VSS_7") (pintype "power_in"))
      (node (ref "IC2") (pin "11") (pinfunction "-V_11") (pintype "power_in"))
      (node (ref "IC2") (pin "5") (pinfunction "+IN_5") (pintype "input"))
      (node (ref "IC3") (pin "7") (pinfunction "VSS_7") (pintype "power_in"))
      (node (ref "LDR_A") (pin "1") (pinfunction "1_1") (pintype "passive"))
      (node (ref "LDR_B") (pin "1") (pinfunction "1_1") (pintype "passive"))
      (node (ref "LDR_C") (pin "1") (pinfunction "1_1") (pintype "passive"))
      (node (ref "LDR_D") (pin "1") (pinfunction "1_1") (pintype "passive"))
      (node (ref "MIC1") (pin "2") (pinfunction "2_2") (pintype "passive"))
      (node (ref "MIC2") (pin "2") (pinfunction "2_2") (pintype "passive"))
      (node (ref "Q1") (pin "1") (pinfunction "S_1") (pintype "passive"))
      (node (ref "Q1") (pin "2") (pinfunction "S_2") (pintype "passive"))
      (node (ref "Q1") (pin "3") (pinfunction "S_3") (pintype "passive"))
      (node (ref "Q2") (pin "1") (pinfunction "S_1") (pintype "passive"))
      (node (ref "Q2") (pin "2") (pinfunction "S_2") (pintype "passive"))
      (node (ref "Q2") (pin "3") (pinfunction "S_3") (pintype "passive"))
      (node (ref "R11") (pin "1") (pinfunction "1_1") (pintype "passive"))
      (node (ref "R12") (pin "1") (pinfunction "1_1") (pintype "passive"))
      (node (ref "R13") (pin "1") (pinfunction "1_1") (pintype "passive"))
      (node (ref "R14") (pin "1") (pinfunction "1_1") (pintype "passive"))
      (node (ref "R3") (pin "2") (pinfunction "2_2") (pintype "passive"))
      (node (ref "R4") (pin "1") (pinfunction "1_1") (pintype "passive"))
      (node (ref "R45") (pin "1") (pinfunction "1_1") (pintype "passive"))
      (node (ref "R50") (pin "1") (pinfunction "1_1") (pintype "passive"))
      (node (ref "R56") (pin "1") (pinfunction "1_1") (pintype "passive"))
      (node (ref "R59") (pin "2") (pinfunction "2_2") (pintype "passive"))
      (node (ref "R63") (pin "2") (pinfunction "2_2") (pintype "passive"))
      (node (ref "R64") (pin "1") (pinfunction "1_1") (pintype "passive"))
      (node (ref "R65") (pin "2") (pinfunction "2_2") (pintype "passive"))
      (node (ref "R66") (pin "1") (pinfunction "1_1") (pintype "passive"))
      (node (ref "R67") (pin "1") (pinfunction "1_1") (pintype "passive"))
      (node (ref "R68") (pin "2") (pinfunction "2_2") (pintype "passive"))
      (node (ref "R69") (pin "2") (pinfunction "2_2") (pintype "passive"))
      (node (ref "R7") (pin "1") (pinfunction "1_1") (pintype "passive"))
      (node (ref "R70") (pin "1") (pinfunction "1_1") (pintype "passive"))
      (node (ref "R71") (pin "1") (pinfunction "1_1") (pintype "passive"))
      (node (ref "R72") (pin "1") (pinfunction "1_1") (pintype "passive"))
      (node (ref "R73") (pin "1") (pinfunction "1_1") (pintype "passive"))
      (node (ref "R74") (pin "1") (pinfunction "1_1") (pintype "passive"))
      (node (ref "R8") (pin "2") (pinfunction "2_2") (pintype "passive"))
      (node (ref "T1") (pin "E") (pinfunction "E_E") (pintype "passive"))
      (node (ref "TM4") (pin "1") (pinfunction "A_1") (pintype "passive"))
      (node (ref "U$3") (pin "P$7") (pinfunction "P$7_P$7") (pintype "bidirectional"))
      (node (ref "U$7") (pin "P$7") (pinfunction "P$7_P$7") (pintype "bidirectional"))
      (node (ref "U$8") (pin "P$1") (pinfunction "P$1_P$1") (pintype "bidirectional"))
      (node (ref "U$8") (pin "P$2") (pinfunction "P$2_P$2") (pintype "bidirectional"))
      (node (ref "U$8") (pin "P$3") (pinfunction "P$3_P$3") (pintype "bidirectional"))
      (node (ref "U$8") (pin "P$4") (pinfunction "P$4_P$4") (pintype "bidirectional"))
      (node (ref "U$8") (pin "P$5") (pinfunction "P$5_P$5") (pintype "bidirectional"))
      (node (ref "U$8") (pin "P$6") (pinfunction "P$6_P$6") (pintype "bidirectional"))
      (node (ref "U$8") (pin "P$7") (pinfunction "P$7_P$7") (pintype "bidirectional"))
      (node (ref "U$8") (pin "P$8") (pinfunction "P$8_P$8") (pintype "bidirectional"))
      (node (ref "U1") (pin "1") (pinfunction "ADJ/GND_1") (pintype "power_in"))
      (node (ref "U2") (pin "4") (pinfunction "GND_4") (pintype "power_in"))
      (node (ref "ULN1") (pin "9") (pinfunction "9_9") (pintype "bidirectional"))
      (node (ref "ULN2") (pin "9") (pinfunction "9_9") (pintype "bidirectional"))
      (node (ref "ULN3") (pin "9") (pinfunction "9_9") (pintype "bidirectional"))
      (node (ref "ULN4") (pin "9") (pinfunction "9_9") (pintype "bidirectional"))
    )
    (net (code "26") (name "LED_CH_A_IN") (class "Default")
      (node (ref "JP9") (pin "1") (pinfunction "1_1") (pintype "passive"))
      (node (ref "U$9") (pin "P$7") (pinfunction "P$7_P$7") (pintype "bidirectional"))
    )
    (net (code "27") (name "LED_CH_A_OUT") (class "Default")
      (node (ref "R99") (pin "2") (pinfunction "2_2") (pintype "passive"))
      (node (ref "ULN1") (pin "12") (pinfunction "12_12") (pintype "bidirectional"))
    )
    (net (code "28") (name "LED_CH_B_IN") (class "Default")
      (node (ref "JP10") (pin "1") (pinfunction "1_1") (pintype "passive"))
      (node (ref "U$9") (pin "P$8") (pinfunction "P$8_P$8") (pintype "bidirectional"))
    )
    (net (code "29") (name "LED_CH_B_OUT") (class "Default")
      (node (ref "R100") (pin "2") (pinfunction "2_2") (pintype "passive"))
      (node (ref "ULN1") (pin "11") (pinfunction "11_11") (pintype "bidirectional"))
    )
    (net (code "30") (name "LED_CH_C_IN") (class "Default")
      (node (ref "JP11") (pin "1") (pinfunction "1_1") (pintype "passive"))
      (node (ref "U$4") (pin "P$7") (pinfunction "P$7_P$7") (pintype "bidirectional"))
    )
    (net (code "31") (name "LED_CH_C_OUT") (class "Default")
      (node (ref "R101") (pin "2") (pinfunction "2_2") (pintype "passive"))
      (node (ref "ULN2") (pin "12") (pinfunction "12_12") (pintype "bidirectional"))
    )
    (net (code "32") (name "LED_CH_D_IN") (class "Default")
      (node (ref "JP12") (pin "1") (pinfunction "1_1") (pintype "passive"))
      (node (ref "U$4") (pin "P$8") (pinfunction "P$8_P$8") (pintype "bidirectional"))
    )
    (net (code "33") (name "LED_CH_D_OUT") (class "Default")
      (node (ref "R102") (pin "2") (pinfunction "2_2") (pintype "passive"))
      (node (ref "ULN2") (pin "11") (pinfunction "11_11") (pintype "bidirectional"))
    )
    (net (code "34") (name "LED_CH_E_IN") (class "Default")
      (node (ref "JP13") (pin "1") (pinfunction "1_1") (pintype "passive"))
      (node (ref "U$5") (pin "P$15") (pinfunction "P$15_P$15") (pintype "bidirectional"))
    )
    (net (code "35") (name "LED_CH_E_OUT") (class "Default")
      (node (ref "R111") (pin "2") (pinfunction "2_2") (pintype "passive"))
      (node (ref "ULN4") (pin "12") (pinfunction "12_12") (pintype "bidirectional"))
    )
    (net (code "36") (name "LED_CH_F_IN") (class "Default")
      (node (ref "JP14") (pin "1") (pinfunction "1_1") (pintype "passive"))
      (node (ref "U$5") (pin "P$16") (pinfunction "P$16_P$16") (pintype "bidirectional"))
    )
    (net (code "37") (name "LED_CH_F_OUT") (class "Default")
      (node (ref "R112") (pin "2") (pinfunction "2_2") (pintype "passive"))
      (node (ref "ULN4") (pin "11") (pinfunction "11_11") (pintype "bidirectional"))
    )
    (net (code "38") (name "LED_CH_G_IN") (class "Default")
      (node (ref "JP15") (pin "1") (pinfunction "1_1") (pintype "passive"))
      (node (ref "U$6") (pin "P$15") (pinfunction "P$15_P$15") (pintype "bidirectional"))
    )
    (net (code "39") (name "LED_CH_G_OUT") (class "Default")
      (node (ref "R113") (pin "2") (pinfunction "2_2") (pintype "passive"))
      (node (ref "ULN3") (pin "12") (pinfunction "12_12") (pintype "bidirectional"))
    )
    (net (code "40") (name "LED_CH_H_IN") (class "Default")
      (node (ref "JP16") (pin "1") (pinfunction "1_1") (pintype "passive"))
      (node (ref "U$6") (pin "P$16") (pinfunction "P$16_P$16") (pintype "bidirectional"))
    )
    (net (code "41") (name "LED_CH_H_OUT") (class "Default")
      (node (ref "R114") (pin "2") (pinfunction "2_2") (pintype "passive"))
      (node (ref "ULN3") (pin "11") (pinfunction "11_11") (pintype "bidirectional"))
    )
    (net (code "42") (name "LIGHT_SENSOR_A_OUT") (class "Default")
      (node (ref "JP3") (pin "1") (pinfunction "1_1") (pintype "passive"))
      (node (ref "LDR_A") (pin "2") (pinfunction "2_2") (pintype "passive"))
      (node (ref "TM1") (pin "3") (pinfunction "E_3") (pintype "passive"))
    )
    (net (code "43") (name "LIGHT_SENSOR_B_OUT") (class "Default")
      (node (ref "JP4") (pin "1") (pinfunction "1_1") (pintype "passive"))
      (node (ref "LDR_B") (pin "2") (pinfunction "2_2") (pintype "passive"))
      (node (ref "TM2") (pin "3") (pinfunction "E_3") (pintype "passive"))
    )
    (net (code "44") (name "LIGHT_SENSOR_C_OUT") (class "Default")
      (node (ref "JP7") (pin "1") (pinfunction "1_1") (pintype "passive"))
      (node (ref "LDR_C") (pin "2") (pinfunction "2_2") (pintype "passive"))
      (node (ref "TM5") (pin "3") (pinfunction "E_3") (pintype "passive"))
    )
    (net (code "45") (name "LIGHT_SENSOR_D_OUT") (class "Default")
      (node (ref "JP8") (pin "1") (pinfunction "1_1") (pintype "passive"))
      (node (ref "LDR_D") (pin "2") (pinfunction "2_2") (pintype "passive"))
      (node (ref "TM6") (pin "3") (pinfunction "E_3") (pintype "passive"))
    )
    (net (code "46") (name "N$127") (class "Default")
      (node (ref "U$3") (pin "P$8") (pinfunction "P$8_P$8") (pintype "bidirectional"))
    )
    (net (code "47") (name "N$128") (class "Default")
      (node (ref "U$7") (pin "P$8") (pinfunction "P$8_P$8") (pintype "bidirectional"))
    )
    (net (code "48") (name "Net-(C3-Pad1)") (class "Default")
      (node (ref "C3") (pin "1") (pinfunction "1_1") (pintype "passive"))
      (node (ref "C8") (pin "1") (pinfunction "1_1") (pintype "passive"))
      (node (ref "MIC2") (pin "1") (pinfunction "1_1") (pintype "passive"))
      (node (ref "R46") (pin "1") (pinfunction "1_1") (pintype "passive"))
      (node (ref "R50") (pin "2") (pinfunction "2_2") (pintype "passive"))
    )
    (net (code "49") (name "Net-(C4-Pad1)") (class "Default")
      (node (ref "C4") (pin "1") (pinfunction "1_1") (pintype "passive"))
      (node (ref "R58") (pin "2") (pinfunction "2_2") (pintype "passive"))
    )
    (net (code "50") (name "Net-(C7-Pad1)") (class "Default")
      (node (ref "C7") (pin "1") (pinfunction "1_1") (pintype "passive"))
      (node (ref "R41") (pin "1") (pinfunction "1_1") (pintype "passive"))
    )
    (net (code "51") (name "Net-(C7-Pad2)") (class "Default")
      (node (ref "C7") (pin "2") (pinfunction "2_2") (pintype "passive"))
      (node (ref "MIC1") (pin "1") (pinfunction "1_1") (pintype "passive"))
      (node (ref "R60") (pin "2") (pinfunction "2_2") (pintype "passive"))
    )
    (net (code "52") (name "Net-(C8-Pad2)") (class "Default")
      (node (ref "C8") (pin "2") (pinfunction "2_2") (pintype "passive"))
      (node (ref "R51") (pin "1") (pinfunction "1_1") (pintype "passive"))
      (node (ref "T1") (pin "B") (pinfunction "B_B") (pintype "passive"))
    )
    (net (code "53") (name "Net-(D1-PadC)") (class "Default")
      (node (ref "D1") (pin "C") (pinfunction "C_C") (pintype "passive"))
      (node (ref "U$3") (pin "P$11") (pinfunction "P$11_P$11") (pintype "bidirectional"))
    )
    (net (code "54") (name "Net-(D2-PadC)") (class "Default")
      (node (ref "D2") (pin "C") (pinfunction "C_C") (pintype "passive"))
      (node (ref "U$3") (pin "P$12") (pinfunction "P$12_P$12") (pintype "bidirectional"))
    )
    (net (code "55") (name "Net-(D3-PadC)") (class "Default")
      (node (ref "D3") (pin "C") (pinfunction "C_C") (pintype "passive"))
      (node (ref "U$3") (pin "P$13") (pinfunction "P$13_P$13") (pintype "bidirectional"))
    )
    (net (code "56") (name "Net-(D4-PadC)") (class "Default")
      (node (ref "D4") (pin "C") (pinfunction "C_C") (pintype "passive"))
      (node (ref "U$3") (pin "P$14") (pinfunction "P$14_P$14") (pintype "bidirectional"))
    )
    (net (code "57") (name "Net-(D5-PadC)") (class "Default")
      (node (ref "D5") (pin "C") (pinfunction "C_C") (pintype "passive"))
      (node (ref "U$3") (pin "P$15") (pinfunction "P$15_P$15") (pintype "bidirectional"))
    )
    (net (code "58") (name "Net-(D6-PadC)") (class "Default")
      (node (ref "D6") (pin "C") (pinfunction "C_C") (pintype "passive"))
      (node (ref "U$3") (pin "P$16") (pinfunction "P$16_P$16") (pintype "bidirectional"))
    )
    (net (code "59") (name "Net-(D7-PadC)") (class "Default")
      (node (ref "D7") (pin "C") (pinfunction "C_C") (pintype "passive"))
      (node (ref "U$7") (pin "P$11") (pinfunction "P$11_P$11") (pintype "bidirectional"))
    )
    (net (code "60") (name "Net-(D8-PadC)") (class "Default")
      (node (ref "D8") (pin "C") (pinfunction "C_C") (pintype "passive"))
      (node (ref "U$7") (pin "P$12") (pinfunction "P$12_P$12") (pintype "bidirectional"))
    )
    (net (code "61") (name "Net-(D9-PadC)") (class "Default")
      (node (ref "D9") (pin "C") (pinfunction "C_C") (pintype "passive"))
      (node (ref "U$7") (pin "P$13") (pinfunction "P$13_P$13") (pintype "bidirectional"))
    )
    (net (code "62") (name "Net-(D10-PadC)") (class "Default")
      (node (ref "D10") (pin "C") (pinfunction "C_C") (pintype "passive"))
      (node (ref "U$7") (pin "P$14") (pinfunction "P$14_P$14") (pintype "bidirectional"))
    )
    (net (code "63") (name "Net-(D11-PadC)") (class "Default")
      (node (ref "D11") (pin "C") (pinfunction "C_C") (pintype "passive"))
      (node (ref "U$7") (pin "P$15") (pinfunction "P$15_P$15") (pintype "bidirectional"))
    )
    (net (code "64") (name "Net-(D12-PadC)") (class "Default")
      (node (ref "D12") (pin "C") (pinfunction "C_C") (pintype "passive"))
      (node (ref "U$7") (pin "P$16") (pinfunction "P$16_P$16") (pintype "bidirectional"))
    )
    (net (code "65") (name "Net-(D13-A)") (class "Default")
      (node (ref "D13") (pin "1") (pinfunction "A_1") (pintype "passive"))
      (node (ref "IC2") (pin "6") (pinfunction "-IN_6") (pintype "input"))
      (node (ref "R58") (pin "1") (pinfunction "1_1") (pintype "passive"))
      (node (ref "R62") (pin "1") (pinfunction "1_1") (pintype "passive"))
    )
    (net (code "66") (name "Net-(D13-C)") (class "Default")
      (node (ref "D13") (pin "3") (pinfunction "C_3") (pintype "passive"))
      (node (ref "D14") (pin "3") (pinfunction "C_3") (pintype "passive"))
      (node (ref "R61") (pin "1") (pinfunction "1_1") (pintype "passive"))
      (node (ref "R62") (pin "2") (pinfunction "2_2") (pintype "passive"))
    )
    (net (code "67") (name "Net-(D14-A)") (class "Default")
      (node (ref "D14") (pin "1") (pinfunction "A_1") (pintype "passive"))
      (node (ref "IC2") (pin "7") (pinfunction "OUT_7") (pintype "output"))
    )
    (net (code "68") (name "Net-(D15-PadC)") (class "Default")
      (node (ref "D15") (pin "C") (pinfunction "C_C") (pintype "passive"))
      (node (ref "U$10") (pin "P$11") (pinfunction "P$11_P$11") (pintype "bidirectional"))
    )
    (net (code "69") (name "Net-(D16-PadC)") (class "Default")
      (node (ref "D16") (pin "C") (pinfunction "C_C") (pintype "passive"))
      (node (ref "U$10") (pin "P$12") (pinfunction "P$12_P$12") (pintype "bidirectional"))
    )
    (net (code "70") (name "Net-(D17-PadC)") (class "Default")
      (node (ref "D17") (pin "C") (pinfunction "C_C") (pintype "passive"))
      (node (ref "U$10") (pin "P$13") (pinfunction "P$13_P$13") (pintype "bidirectional"))
    )
    (net (code "71") (name "Net-(D18-PadC)") (class "Default")
      (node (ref "D18") (pin "C") (pinfunction "C_C") (pintype "passive"))
      (node (ref "U$10") (pin "P$14") (pinfunction "P$14_P$14") (pintype "bidirectional"))
    )
    (net (code "72") (name "Net-(D19-PadC)") (class "Default")
      (node (ref "D19") (pin "C") (pinfunction "C_C") (pintype "passive"))
      (node (ref "U$10") (pin "P$15") (pinfunction "P$15_P$15") (pintype "bidirectional"))
    )
    (net (code "73") (name "Net-(D20-PadC)") (class "Default")
      (node (ref "D20") (pin "C") (pinfunction "C_C") (pintype "passive"))
      (node (ref "U$10") (pin "P$16") (pinfunction "P$16_P$16") (pintype "bidirectional"))
    )
    (net (code "74") (name "Net-(D21-PadC)") (class "Default")
      (node (ref "D21") (pin "C") (pinfunction "C_C") (pintype "passive"))
      (node (ref "U$11") (pin "P$11") (pinfunction "P$11_P$11") (pintype "bidirectional"))
    )
    (net (code "75") (name "Net-(D22-PadC)") (class "Default")
      (node (ref "D22") (pin "C") (pinfunction "C_C") (pintype "passive"))
      (node (ref "U$11") (pin "P$12") (pinfunction "P$12_P$12") (pintype "bidirectional"))
    )
    (net (code "76") (name "Net-(D23-PadC)") (class "Default")
      (node (ref "D23") (pin "C") (pinfunction "C_C") (pintype "passive"))
      (node (ref "U$11") (pin "P$13") (pinfunction "P$13_P$13") (pintype "bidirectional"))
    )
    (net (code "77") (name "Net-(D24-PadC)") (class "Default")
      (node (ref "D24") (pin "C") (pinfunction "C_C") (pintype "passive"))
      (node (ref "U$11") (pin "P$14") (pinfunction "P$14_P$14") (pintype "bidirectional"))
    )
    (net (code "78") (name "Net-(D25-PadC)") (class "Default")
      (node (ref "D25") (pin "C") (pinfunction "C_C") (pintype "passive"))
      (node (ref "U$11") (pin "P$15") (pinfunction "P$15_P$15") (pintype "bidirectional"))
    )
    (net (code "79") (name "Net-(D26-PadC)") (class "Default")
      (node (ref "D26") (pin "C") (pinfunction "C_C") (pintype "passive"))
      (node (ref "U$11") (pin "P$16") (pinfunction "P$16_P$16") (pintype "bidirectional"))
    )
    (net (code "80") (name "Net-(IC2A-+IN)") (class "Default")
      (node (ref "IC2") (pin "3") (pinfunction "+IN_3") (pintype "input"))
      (node (ref "R42") (pin "2") (pinfunction "2_2") (pintype "passive"))
      (node (ref "R45") (pin "2") (pinfunction "2_2") (pintype "passive"))
    )
    (net (code "81") (name "Net-(IC2A--IN)") (class "Default")
      (node (ref "IC2") (pin "2") (pinfunction "-IN_2") (pintype "input"))
      (node (ref "R41") (pin "2") (pinfunction "2_2") (pintype "passive"))
      (node (ref "TM3") (pin "2") (pinfunction "S_2") (pintype "passive"))
    )
    (net (code "82") (name "Net-(IC2A-OUT)") (class "Default")
      (node (ref "C4") (pin "2") (pinfunction "2_2") (pintype "passive"))
      (node (ref "IC2") (pin "1") (pinfunction "OUT_1") (pintype "output"))
      (node (ref "R43") (pin "1") (pinfunction "1_1") (pintype "passive"))
    )
    (net (code "83") (name "Net-(IC2B-+IN)") (class "Default")
      (node (ref "IC2") (pin "10") (pinfunction "+IN_10") (pintype "input"))
      (node (ref "R49") (pin "2") (pinfunction "2_2") (pintype "passive"))
      (node (ref "R55") (pin "2") (pinfunction "2_2") (pintype "passive"))
    )
    (net (code "84") (name "Net-(IC2B--IN)") (class "Default")
      (node (ref "IC2") (pin "9") (pinfunction "-IN_9") (pintype "input"))
      (node (ref "R48") (pin "1") (pinfunction "1_1") (pintype "passive"))
      (node (ref "R56") (pin "2") (pinfunction "2_2") (pintype "passive"))
    )
    (net (code "85") (name "Net-(IC2B-OUT)") (class "Default")
      (node (ref "IC2") (pin "8") (pinfunction "OUT_8") (pintype "output"))
      (node (ref "R47") (pin "1") (pinfunction "1_1") (pintype "passive"))
      (node (ref "R49") (pin "1") (pinfunction "1_1") (pintype "passive"))
    )
    (net (code "86") (name "Net-(IC2D-+IN)") (class "Default")
      (node (ref "C5") (pin "1") (pinfunction "1_1") (pintype "passive"))
      (node (ref "IC2") (pin "12") (pinfunction "+IN_12") (pintype "input"))
      (node (ref "R59") (pin "1") (pinfunction "1_1") (pintype "passive"))
      (node (ref "R61") (pin "2") (pinfunction "2_2") (pintype "passive"))
    )
    (net (code "87") (name "Net-(IC2D--IN)") (class "Default")
      (node (ref "IC2") (pin "13") (pinfunction "-IN_13") (pintype "input"))
      (node (ref "R44") (pin "1") (pinfunction "1_1") (pintype "passive"))
    )
    (net (code "88") (name "Net-(IC2D-OUT)") (class "Default")
      (node (ref "IC2") (pin "14") (pinfunction "OUT_14") (pintype "output"))
      (node (ref "R44") (pin "2") (pinfunction "2_2") (pintype "passive"))
      (node (ref "R55") (pin "1") (pinfunction "1_1") (pintype "passive"))
    )
    (net (code "89") (name "Net-(JP1-Pad1)") (class "Default")
      (node (ref "JP1") (pin "1") (pinfunction "1_1") (pintype "passive"))
      (node (ref "R2") (pin "1") (pinfunction "1_1") (pintype "passive"))
    )
    (net (code "90") (name "Net-(JP2-Pad1)") (class "Default")
      (node (ref "JP2") (pin "1") (pinfunction "1_1") (pintype "passive"))
      (node (ref "R1") (pin "1") (pinfunction "1_1") (pintype "passive"))
    )
    (net (code "91") (name "Net-(JP5-Pad1)") (class "Default")
      (node (ref "JP5") (pin "1") (pinfunction "1_1") (pintype "passive"))
      (node (ref "R47") (pin "2") (pinfunction "2_2") (pintype "passive"))
    )
    (net (code "92") (name "Net-(LED1-C)") (class "Default")
      (node (ref "LED1") (pin "K") (pinfunction "C_K") (pintype "passive"))
      (node (ref "R99") (pin "1") (pinfunction "1_1") (pintype "passive"))
    )
    (net (code "93") (name "Net-(LED2-C)") (class "Default")
      (node (ref "LED2") (pin "K") (pinfunction "C_K") (pintype "passive"))
      (node (ref "R100") (pin "1") (pinfunction "1_1") (pintype "passive"))
    )
    (net (code "94") (name "Net-(LED3-C)") (class "Default")
      (node (ref "LED3") (pin "K") (pinfunction "C_K") (pintype "passive"))
      (node (ref "R101") (pin "1") (pinfunction "1_1") (pintype "passive"))
    )
    (net (code "95") (name "Net-(LED4-C)") (class "Default")
      (node (ref "LED4") (pin "K") (pinfunction "C_K") (pintype "passive"))
      (node (ref "R102") (pin "1") (pinfunction "1_1") (pintype "passive"))
    )
    (net (code "96") (name "Net-(LED5-C)") (class "Default")
      (node (ref "LED5") (pin "K") (pinfunction "C_K") (pintype "passive"))
      (node (ref "R111") (pin "1") (pinfunction "1_1") (pintype "passive"))
    )
    (net (code "97") (name "Net-(LED6-C)") (class "Default")
      (node (ref "LED6") (pin "K") (pinfunction "C_K") (pintype "passive"))
      (node (ref "R112") (pin "1") (pinfunction "1_1") (pintype "passive"))
    )
    (net (code "98") (name "Net-(LED7-C)") (class "Default")
      (node (ref "LED7") (pin "K") (pinfunction "C_K") (pintype "passive"))
      (node (ref "R113") (pin "1") (pinfunction "1_1") (pintype "passive"))
    )
    (net (code "99") (name "Net-(LED8-C)") (class "Default")
      (node (ref "LED8") (pin "K") (pinfunction "C_K") (pintype "passive"))
      (node (ref "R114") (pin "1") (pinfunction "1_1") (pintype "passive"))
    )
    (net (code "100") (name "Net-(Q1-D-Pad5)") (class "Default")
      (node (ref "Q1") (pin "5") (pinfunction "D_5") (pintype "passive"))
      (node (ref "Q1") (pin "6") (pinfunction "D_6") (pintype "passive"))
      (node (ref "Q1") (pin "7") (pinfunction "D_7") (pintype "passive"))
      (node (ref "Q1") (pin "8") (pinfunction "D_8") (pintype "passive"))
      (node (ref "U$1") (pin "P$1") (pinfunction "P$1_P$1") (pintype "bidirectional"))
    )
    (net (code "101") (name "Net-(Q1-G)") (class "Default")
      (node (ref "Q1") (pin "4") (pinfunction "G_4") (pintype "passive"))
      (node (ref "R2") (pin "2") (pinfunction "2_2") (pintype "passive"))
    )
    (net (code "102") (name "Net-(Q2-D-Pad5)") (class "Default")
      (node (ref "Q2") (pin "5") (pinfunction "D_5") (pintype "passive"))
      (node (ref "Q2") (pin "6") (pinfunction "D_6") (pintype "passive"))
      (node (ref "Q2") (pin "7") (pinfunction "D_7") (pintype "passive"))
      (node (ref "Q2") (pin "8") (pinfunction "D_8") (pintype "passive"))
      (node (ref "U$2") (pin "P$1") (pinfunction "P$1_P$1") (pintype "bidirectional"))
    )
    (net (code "103") (name "Net-(Q2-G)") (class "Default")
      (node (ref "Q2") (pin "4") (pinfunction "G_4") (pintype "passive"))
      (node (ref "R1") (pin "2") (pinfunction "2_2") (pintype "passive"))
    )
    (net (code "104") (name "Net-(TM1-S)") (class "Default")
      (node (ref "R39") (pin "2") (pinfunction "2_2") (pintype "passive"))
      (node (ref "TM1") (pin "2") (pinfunction "S_2") (pintype "passive"))
    )
    (net (code "105") (name "Net-(TM2-S)") (class "Default")
      (node (ref "R40") (pin "2") (pinfunction "2_2") (pintype "passive"))
      (node (ref "TM2") (pin "2") (pinfunction "S_2") (pintype "passive"))
    )
    (net (code "106") (name "Net-(TM3-E)") (class "Default")
      (node (ref "R43") (pin "2") (pinfunction "2_2") (pintype "passive"))
      (node (ref "TM3") (pin "3") (pinfunction "E_3") (pintype "passive"))
    )
    (net (code "107") (name "Net-(TM4-S)") (class "Default")
      (node (ref "TM4") (pin "2") (pinfunction "S_2") (pintype "passive"))
      (node (ref "U2") (pin "2") (pinfunction "1IN-_2") (pintype "input"))
    )
    (net (code "108") (name "Net-(TM5-S)") (class "Default")
      (node (ref "R54") (pin "2") (pinfunction "2_2") (pintype "passive"))
      (node (ref "TM5") (pin "2") (pinfunction "S_2") (pintype "passive"))
    )
    (net (code "109") (name "Net-(TM6-S)") (class "Default")
      (node (ref "R57") (pin "2") (pinfunction "2_2") (pintype "passive"))
      (node (ref "TM6") (pin "2") (pinfunction "S_2") (pintype "passive"))
    )
    (net (code "110") (name "Net-(U$3-PadP$1)") (class "Default")
      (node (ref "U$3") (pin "P$1") (pinfunction "P$1_P$1") (pintype "bidirectional"))
      (node (ref "ULN1") (pin "18") (pinfunction "18_18") (pintype "bidirectional"))
    )
    (net (code "111") (name "Net-(U$3-PadP$2)") (class "Default")
      (node (ref "U$3") (pin "P$2") (pinfunction "P$2_P$2") (pintype "bidirectional"))
      (node (ref "ULN1") (pin "17") (pinfunction "17_17") (pintype "bidirectional"))
    )
    (net (code "112") (name "Net-(U$3-PadP$3)") (class "Default")
      (node (ref "U$3") (pin "P$3") (pinfunction "P$3_P$3") (pintype "bidirectional"))
      (node (ref "ULN1") (pin "16") (pinfunction "16_16") (pintype "bidirectional"))
    )
    (net (code "113") (name "Net-(U$3-PadP$4)") (class "Default")
      (node (ref "U$3") (pin "P$4") (pinfunction "P$4_P$4") (pintype "bidirectional"))
      (node (ref "ULN1") (pin "15") (pinfunction "15_15") (pintype "bidirectional"))
    )
    (net (code "114") (name "Net-(U$3-PadP$5)") (class "Default")
      (node (ref "U$3") (pin "P$5") (pinfunction "P$5_P$5") (pintype "bidirectional"))
      (node (ref "ULN1") (pin "14") (pinfunction "14_14") (pintype "bidirectional"))
    )
    (net (code "115") (name "Net-(U$3-PadP$6)") (class "Default")
      (node (ref "U$3") (pin "P$6") (pinfunction "P$6_P$6") (pintype "bidirectional"))
      (node (ref "ULN1") (pin "13") (pinfunction "13_13") (pintype "bidirectional"))
    )
    (net (code "116") (name "Net-(U$4-PadP$9)") (class "Default")
      (node (ref "U$4") (pin "P$9") (pinfunction "P$9_P$9") (pintype "bidirectional"))
      (node (ref "ULN2") (pin "8") (pinfunction "8_8") (pintype "bidirectional"))
    )
    (net (code "117") (name "Net-(U$4-PadP$10)") (class "Default")
      (node (ref "U$4") (pin "P$10") (pinfunction "P$10_P$10") (pintype "bidirectional"))
      (node (ref "ULN2") (pin "7") (pinfunction "7_7") (pintype "bidirectional"))
    )
    (net (code "118") (name "Net-(U$4-PadP$11)") (class "Default")
      (node (ref "U$4") (pin "P$11") (pinfunction "P$11_P$11") (pintype "bidirectional"))
      (node (ref "ULN2") (pin "6") (pinfunction "6_6") (pintype "bidirectional"))
    )
    (net (code "119") (name "Net-(U$4-PadP$12)") (class "Default")
      (node (ref "U$4") (pin "P$12") (pinfunction "P$12_P$12") (pintype "bidirectional"))
      (node (ref "ULN2") (pin "5") (pinfunction "5_5") (pintype "bidirectional"))
    )
    (net (code "120") (name "Net-(U$4-PadP$13)") (class "Default")
      (node (ref "U$4") (pin "P$13") (pinfunction "P$13_P$13") (pintype "bidirectional"))
      (node (ref "ULN2") (pin "4") (pinfunction "4_4") (pintype "bidirectional"))
    )
    (net (code "121") (name "Net-(U$4-PadP$14)") (class "Default")
      (node (ref "U$4") (pin "P$14") (pinfunction "P$14_P$14") (pintype "bidirectional"))
      (node (ref "ULN2") (pin "3") (pinfunction "3_3") (pintype "bidirectional"))
    )
    (net (code "122") (name "Net-(U$4-PadP$15)") (class "Default")
      (node (ref "U$4") (pin "P$15") (pinfunction "P$15_P$15") (pintype "bidirectional"))
      (node (ref "ULN2") (pin "2") (pinfunction "2_2") (pintype "bidirectional"))
    )
    (net (code "123") (name "Net-(U$4-PadP$16)") (class "Default")
      (node (ref "U$4") (pin "P$16") (pinfunction "P$16_P$16") (pintype "bidirectional"))
      (node (ref "ULN2") (pin "1") (pinfunction "1_1") (pintype "bidirectional"))
    )
    (net (code "124") (name "Net-(U$5-PadP$1)") (class "Default")
      (node (ref "U$5") (pin "P$1") (pinfunction "P$1_P$1") (pintype "bidirectional"))
      (node (ref "ULN4") (pin "8") (pinfunction "8_8") (pintype "bidirectional"))
    )
    (net (code "125") (name "Net-(U$5-PadP$2)") (class "Default")
      (node (ref "U$5") (pin "P$2") (pinfunction "P$2_P$2") (pintype "bidirectional"))
      (node (ref "ULN4") (pin "7") (pinfunction "7_7") (pintype "bidirectional"))
    )
    (net (code "126") (name "Net-(U$5-PadP$3)") (class "Default")
      (node (ref "U$5") (pin "P$3") (pinfunction "P$3_P$3") (pintype "bidirectional"))
      (node (ref "ULN4") (pin "6") (pinfunction "6_6") (pintype "bidirectional"))
    )
    (net (code "127") (name "Net-(U$5-PadP$4)") (class "Default")
      (node (ref "U$5") (pin "P$4") (pinfunction "P$4_P$4") (pintype "bidirectional"))
      (node (ref "ULN4") (pin "5") (pinfunction "5_5") (pintype "bidirectional"))
    )
    (net (code "128") (name "Net-(U$5-PadP$5)") (class "Default")
      (node (ref "U$5") (pin "P$5") (pinfunction "P$5_P$5") (pintype "bidirectional"))
      (node (ref "ULN4") (pin "4") (pinfunction "4_4") (pintype "bidirectional"))
    )
    (net (code "129") (name "Net-(U$5-PadP$6)") (class "Default")
      (node (ref "U$5") (pin "P$6") (pinfunction "P$6_P$6") (pintype "bidirectional"))
      (node (ref "ULN4") (pin "3") (pinfunction "3_3") (pintype "bidirectional"))
    )
    (net (code "130") (name "Net-(U$5-PadP$7)") (class "Default")
      (node (ref "U$5") (pin "P$7") (pinfunction "P$7_P$7") (pintype "bidirectional"))
      (node (ref "ULN4") (pin "2") (pinfunction "2_2") (pintype "bidirectional"))
    )
    (net (code "131") (name "Net-(U$5-PadP$8)") (class "Default")
      (node (ref "U$5") (pin "P$8") (pinfunction "P$8_P$8") (pintype "bidirectional"))
      (node (ref "ULN4") (pin "1") (pinfunction "1_1") (pintype "bidirectional"))
    )
    (net (code "132") (name "Net-(U$6-PadP$1)") (class "Default")
      (node (ref "U$6") (pin "P$1") (pinfunction "P$1_P$1") (pintype "bidirectional"))
      (node (ref "ULN3") (pin "8") (pinfunction "8_8") (pintype "bidirectional"))
    )
    (net (code "133") (name "Net-(U$6-PadP$2)") (class "Default")
      (node (ref "U$6") (pin "P$2") (pinfunction "P$2_P$2") (pintype "bidirectional"))
      (node (ref "ULN3") (pin "7") (pinfunction "7_7") (pintype "bidirectional"))
    )
    (net (code "134") (name "Net-(U$6-PadP$3)") (class "Default")
      (node (ref "U$6") (pin "P$3") (pinfunction "P$3_P$3") (pintype "bidirectional"))
      (node (ref "ULN3") (pin "6") (pinfunction "6_6") (pintype "bidirectional"))
    )
    (net (code "135") (name "Net-(U$6-PadP$4)") (class "Default")
      (node (ref "U$6") (pin "P$4") (pinfunction "P$4_P$4") (pintype "bidirectional"))
      (node (ref "ULN3") (pin "5") (pinfunction "5_5") (pintype "bidirectional"))
    )
    (net (code "136") (name "Net-(U$6-PadP$5)") (class "Default")
      (node (ref "U$6") (pin "P$5") (pinfunction "P$5_P$5") (pintype "bidirectional"))
      (node (ref "ULN3") (pin "4") (pinfunction "4_4") (pintype "bidirectional"))
    )
    (net (code "137") (name "Net-(U$6-PadP$6)") (class "Default")
      (node (ref "U$6") (pin "P$6") (pinfunction "P$6_P$6") (pintype "bidirectional"))
      (node (ref "ULN3") (pin "3") (pinfunction "3_3") (pintype "bidirectional"))
    )
    (net (code "138") (name "Net-(U$6-PadP$7)") (class "Default")
      (node (ref "U$6") (pin "P$7") (pinfunction "P$7_P$7") (pintype "bidirectional"))
      (node (ref "ULN3") (pin "2") (pinfunction "2_2") (pintype "bidirectional"))
    )
    (net (code "139") (name "Net-(U$6-PadP$8)") (class "Default")
      (node (ref "U$6") (pin "P$8") (pinfunction "P$8_P$8") (pintype "bidirectional"))
      (node (ref "ULN3") (pin "1") (pinfunction "1_1") (pintype "bidirectional"))
    )
    (net (code "140") (name "Net-(U$7-PadP$1)") (class "Default")
      (node (ref "U$7") (pin "P$1") (pinfunction "P$1_P$1") (pintype "bidirectional"))
      (node (ref "ULN2") (pin "18") (pinfunction "18_18") (pintype "bidirectional"))
    )
    (net (code "141") (name "Net-(U$7-PadP$2)") (class "Default")
      (node (ref "U$7") (pin "P$2") (pinfunction "P$2_P$2") (pintype "bidirectional"))
      (node (ref "ULN2") (pin "17") (pinfunction "17_17") (pintype "bidirectional"))
    )
    (net (code "142") (name "Net-(U$7-PadP$3)") (class "Default")
      (node (ref "U$7") (pin "P$3") (pinfunction "P$3_P$3") (pintype "bidirectional"))
      (node (ref "ULN2") (pin "16") (pinfunction "16_16") (pintype "bidirectional"))
    )
    (net (code "143") (name "Net-(U$7-PadP$4)") (class "Default")
      (node (ref "U$7") (pin "P$4") (pinfunction "P$4_P$4") (pintype "bidirectional"))
      (node (ref "ULN2") (pin "15") (pinfunction "15_15") (pintype "bidirectional"))
    )
    (net (code "144") (name "Net-(U$7-PadP$5)") (class "Default")
      (node (ref "U$7") (pin "P$5") (pinfunction "P$5_P$5") (pintype "bidirectional"))
      (node (ref "ULN2") (pin "14") (pinfunction "14_14") (pintype "bidirectional"))
    )
    (net (code "145") (name "Net-(U$7-PadP$6)") (class "Default")
      (node (ref "U$7") (pin "P$6") (pinfunction "P$6_P$6") (pintype "bidirectional"))
      (node (ref "ULN2") (pin "13") (pinfunction "13_13") (pintype "bidirectional"))
    )
    (net (code "146") (name "Net-(U$9-PadP$9)") (class "Default")
      (node (ref "U$9") (pin "P$9") (pinfunction "P$9_P$9") (pintype "bidirectional"))
      (node (ref "ULN1") (pin "8") (pinfunction "8_8") (pintype "bidirectional"))
    )
    (net (code "147") (name "Net-(U$9-PadP$10)") (class "Default")
      (node (ref "U$9") (pin "P$10") (pinfunction "P$10_P$10") (pintype "bidirectional"))
      (node (ref "ULN1") (pin "7") (pinfunction "7_7") (pintype "bidirectional"))
    )
    (net (code "148") (name "Net-(U$9-PadP$11)") (class "Default")
      (node (ref "U$9") (pin "P$11") (pinfunction "P$11_P$11") (pintype "bidirectional"))
      (node (ref "ULN1") (pin "6") (pinfunction "6_6") (pintype "bidirectional"))
    )
    (net (code "149") (name "Net-(U$9-PadP$12)") (class "Default")
      (node (ref "U$9") (pin "P$12") (pinfunction "P$12_P$12") (pintype "bidirectional"))
      (node (ref "ULN1") (pin "5") (pinfunction "5_5") (pintype "bidirectional"))
    )
    (net (code "150") (name "Net-(U$9-PadP$13)") (class "Default")
      (node (ref "U$9") (pin "P$13") (pinfunction "P$13_P$13") (pintype "bidirectional"))
      (node (ref "ULN1") (pin "4") (pinfunction "4_4") (pintype "bidirectional"))
    )
    (net (code "151") (name "Net-(U$9-PadP$14)") (class "Default")
      (node (ref "U$9") (pin "P$14") (pinfunction "P$14_P$14") (pintype "bidirectional"))
      (node (ref "ULN1") (pin "3") (pinfunction "3_3") (pintype "bidirectional"))
    )
    (net (code "152") (name "Net-(U$9-PadP$15)") (class "Default")
      (node (ref "U$9") (pin "P$15") (pinfunction "P$15_P$15") (pintype "bidirectional"))
      (node (ref "ULN1") (pin "2") (pinfunction "2_2") (pintype "bidirectional"))
    )
    (net (code "153") (name "Net-(U$9-PadP$16)") (class "Default")
      (node (ref "U$9") (pin "P$16") (pinfunction "P$16_P$16") (pintype "bidirectional"))
      (node (ref "ULN1") (pin "1") (pinfunction "1_1") (pintype "bidirectional"))
    )
    (net (code "154") (name "Net-(U$10-PadP$1)") (class "Default")
      (node (ref "U$10") (pin "P$1") (pinfunction "P$1_P$1") (pintype "bidirectional"))
      (node (ref "ULN4") (pin "18") (pinfunction "18_18") (pintype "bidirectional"))
    )
    (net (code "155") (name "Net-(U$10-PadP$2)") (class "Default")
      (node (ref "U$10") (pin "P$2") (pinfunction "P$2_P$2") (pintype "bidirectional"))
      (node (ref "ULN4") (pin "17") (pinfunction "17_17") (pintype "bidirectional"))
    )
    (net (code "156") (name "Net-(U$10-PadP$3)") (class "Default")
      (node (ref "U$10") (pin "P$3") (pinfunction "P$3_P$3") (pintype "bidirectional"))
      (node (ref "ULN4") (pin "16") (pinfunction "16_16") (pintype "bidirectional"))
    )
    (net (code "157") (name "Net-(U$10-PadP$4)") (class "Default")
      (node (ref "U$10") (pin "P$4") (pinfunction "P$4_P$4") (pintype "bidirectional"))
      (node (ref "ULN4") (pin "15") (pinfunction "15_15") (pintype "bidirectional"))
    )
    (net (code "158") (name "Net-(U$10-PadP$5)") (class "Default")
      (node (ref "U$10") (pin "P$5") (pinfunction "P$5_P$5") (pintype "bidirectional"))
      (node (ref "ULN4") (pin "14") (pinfunction "14_14") (pintype "bidirectional"))
    )
    (net (code "159") (name "Net-(U$10-PadP$6)") (class "Default")
      (node (ref "U$10") (pin "P$6") (pinfunction "P$6_P$6") (pintype "bidirectional"))
      (node (ref "ULN4") (pin "13") (pinfunction "13_13") (pintype "bidirectional"))
    )
    (net (code "160") (name "Net-(U$11-PadP$1)") (class "Default")
      (node (ref "U$11") (pin "P$1") (pinfunction "P$1_P$1") (pintype "bidirectional"))
      (node (ref "ULN3") (pin "18") (pinfunction "18_18") (pintype "bidirectional"))
    )
    (net (code "161") (name "Net-(U$11-PadP$2)") (class "Default")
      (node (ref "U$11") (pin "P$2") (pinfunction "P$2_P$2") (pintype "bidirectional"))
      (node (ref "ULN3") (pin "17") (pinfunction "17_17") (pintype "bidirectional"))
    )
    (net (code "162") (name "Net-(U$11-PadP$3)") (class "Default")
      (node (ref "U$11") (pin "P$3") (pinfunction "P$3_P$3") (pintype "bidirectional"))
      (node (ref "ULN3") (pin "16") (pinfunction "16_16") (pintype "bidirectional"))
    )
    (net (code "163") (name "Net-(U$11-PadP$4)") (class "Default")
      (node (ref "U$11") (pin "P$4") (pinfunction "P$4_P$4") (pintype "bidirectional"))
      (node (ref "ULN3") (pin "15") (pinfunction "15_15") (pintype "bidirectional"))
    )
    (net (code "164") (name "Net-(U$11-PadP$5)") (class "Default")
      (node (ref "U$11") (pin "P$5") (pinfunction "P$5_P$5") (pintype "bidirectional"))
      (node (ref "ULN3") (pin "14") (pinfunction "14_14") (pintype "bidirectional"))
    )
    (net (code "165") (name "Net-(U$11-PadP$6)") (class "Default")
      (node (ref "U$11") (pin "P$6") (pinfunction "P$6_P$6") (pintype "bidirectional"))
      (node (ref "ULN3") (pin "13") (pinfunction "13_13") (pintype "bidirectional"))
    )
    (net (code "166") (name "Net-(U1-IN)") (class "Default")
      (node (ref "BT2") (pin "+") (pinfunction "+_+") (pintype "power_in"))
      (node (ref "C1") (pin "2") (pinfunction "2_2") (pintype "passive"))
      (node (ref "U1") (pin "3") (pinfunction "IN_3") (pintype "input"))
    )
    (net (code "167") (name "Net-(U2-1IN+)") (class "Default")
      (node (ref "C9") (pin "2") (pinfunction "2_2") (pintype "passive"))
      (node (ref "R52") (pin "1") (pinfunction "1_1") (pintype "passive"))
      (node (ref "T1") (pin "C") (pinfunction "C_C") (pintype "passive"))
      (node (ref "U2") (pin "3") (pinfunction "1IN+_3") (pintype "input"))
    )
    (net (code "168") (name "Net-(U2-1OUT)") (class "Default")
      (node (ref "JP6") (pin "1") (pinfunction "1_1") (pintype "passive"))
      (node (ref "R53") (pin "1") (pinfunction "1_1") (pintype "passive"))
      (node (ref "U2") (pin "1") (pinfunction "1OUT_1") (pintype "output"))
    )
    (net (code "169") (name "VDD") (class "Default")
      (node (ref "C11") (pin "1") (pinfunction "1_1") (pintype "passive"))
      (node (ref "C2") (pin "2") (pinfunction "2_2") (pintype "passive"))
      (node (ref "C6") (pin "1") (pinfunction "1_1") (pintype "passive"))
      (node (ref "D1") (pin "A") (pinfunction "A_A") (pintype "passive"))
      (node (ref "D10") (pin "A") (pinfunction "A_A") (pintype "passive"))
      (node (ref "D11") (pin "A") (pinfunction "A_A") (pintype "passive"))
      (node (ref "D12") (pin "A") (pinfunction "A_A") (pintype "passive"))
      (node (ref "D15") (pin "A") (pinfunction "A_A") (pintype "passive"))
      (node (ref "D16") (pin "A") (pinfunction "A_A") (pintype "passive"))
      (node (ref "D17") (pin "A") (pinfunction "A_A") (pintype "passive"))
      (node (ref "D18") (pin "A") (pinfunction "A_A") (pintype "passive"))
      (node (ref "D19") (pin "A") (pinfunction "A_A") (pintype "passive"))
      (node (ref "D2") (pin "A") (pinfunction "A_A") (pintype "passive"))
      (node (ref "D20") (pin "A") (pinfunction "A_A") (pintype "passive"))
      (node (ref "D21") (pin "A") (pinfunction "A_A") (pintype "passive"))
      (node (ref "D22") (pin "A") (pinfunction "A_A") (pintype "passive"))
      (node (ref "D23") (pin "A") (pinfunction "A_A") (pintype "passive"))
      (node (ref "D24") (pin "A") (pinfunction "A_A") (pintype "passive"))
      (node (ref "D25") (pin "A") (pinfunction "A_A") (pintype "passive"))
      (node (ref "D26") (pin "A") (pinfunction "A_A") (pintype "passive"))
      (node (ref "D3") (pin "A") (pinfunction "A_A") (pintype "passive"))
      (node (ref "D4") (pin "A") (pinfunction "A_A") (pintype "passive"))
      (node (ref "D5") (pin "A") (pinfunction "A_A") (pintype "passive"))
      (node (ref "D6") (pin "A") (pinfunction "A_A") (pintype "passive"))
      (node (ref "D7") (pin "A") (pinfunction "A_A") (pintype "passive"))
      (node (ref "D8") (pin "A") (pinfunction "A_A") (pintype "passive"))
      (node (ref "D9") (pin "A") (pinfunction "A_A") (pintype "passive"))
      (node (ref "IC1") (pin "14") (pinfunction "VDD_14") (pintype "power_in"))
      (node (ref "IC2") (pin "4") (pinfunction "+V_4") (pintype "power_in"))
      (node (ref "IC3") (pin "14") (pinfunction "VDD_14") (pintype "power_in"))
      (node (ref "LED1") (pin "A") (pinfunction "A_A") (pintype "passive"))
      (node (ref "LED2") (pin "A") (pinfunction "A_A") (pintype "passive"))
      (node (ref "LED3") (pin "A") (pinfunction "A_A") (pintype "passive"))
      (node (ref "LED4") (pin "A") (pinfunction "A_A") (pintype "passive"))
      (node (ref "LED5") (pin "A") (pinfunction "A_A") (pintype "passive"))
      (node (ref "LED6") (pin "A") (pinfunction "A_A") (pintype "passive"))
      (node (ref "LED7") (pin "A") (pinfunction "A_A") (pintype "passive"))
      (node (ref "LED8") (pin "A") (pinfunction "A_A") (pintype "passive"))
      (node (ref "R39") (pin "1") (pinfunction "1_1") (pintype "passive"))
      (node (ref "R40") (pin "1") (pinfunction "1_1") (pintype "passive"))
      (node (ref "R42") (pin "1") (pinfunction "1_1") (pintype "passive"))
      (node (ref "R46") (pin "2") (pinfunction "2_2") (pintype "passive"))
      (node (ref "R48") (pin "2") (pinfunction "2_2") (pintype "passive"))
      (node (ref "R51") (pin "2") (pinfunction "2_2") (pintype "passive"))
      (node (ref "R52") (pin "2") (pinfunction "2_2") (pintype "passive"))
      (node (ref "R53") (pin "2") (pinfunction "2_2") (pintype "passive"))
      (node (ref "R54") (pin "1") (pinfunction "1_1") (pintype "passive"))
      (node (ref "R57") (pin "1") (pinfunction "1_1") (pintype "passive"))
      (node (ref "R60") (pin "1") (pinfunction "1_1") (pintype "passive"))
      (node (ref "TM4") (pin "3") (pinfunction "E_3") (pintype "passive"))
      (node (ref "U$1") (pin "P$2") (pinfunction "P$2_P$2") (pintype "bidirectional"))
      (node (ref "U$2") (pin "P$2") (pinfunction "P$2_P$2") (pintype "bidirectional"))
      (node (ref "U1") (pin "2") (pinfunction "OUT_2") (pintype "output"))
      (node (ref "U1") (pin "4") (pinfunction "4_4") (pintype "passive"))
      (node (ref "U2") (pin "8") (pinfunction "VCC_8") (pintype "power_in"))
      (node (ref "ULN1") (pin "10") (pinfunction "10_10") (pintype "bidirectional"))
      (node (ref "ULN2") (pin "10") (pinfunction "10_10") (pintype "bidirectional"))
      (node (ref "ULN3") (pin "10") (pinfunction "10_10") (pintype "bidirectional"))
      (node (ref "ULN4") (pin "10") (pinfunction "10_10") (pintype "bidirectional"))
    )
    (net (code "170") (name "unconnected-(TM1-A-Pad1)") (class "Default")
      (node (ref "TM1") (pin "1") (pinfunction "A_1") (pintype "passive"))
    )
    (net (code "171") (name "unconnected-(TM2-A-Pad1)") (class "Default")
      (node (ref "TM2") (pin "1") (pinfunction "A_1") (pintype "passive"))
    )
    (net (code "172") (name "unconnected-(TM3-A-Pad1)") (class "Default")
      (node (ref "TM3") (pin "1") (pinfunction "A_1") (pintype "passive"))
    )
    (net (code "173") (name "unconnected-(TM5-A-Pad1)") (class "Default")
      (node (ref "TM5") (pin "1") (pinfunction "A_1") (pintype "passive"))
    )
    (net (code "174") (name "unconnected-(TM6-A-Pad1)") (class "Default")
      (node (ref "TM6") (pin "1") (pinfunction "A_1") (pintype "passive"))
    )
    (net (code "175") (name "unconnected-(U$8-PadP$9)") (class "Default")
      (node (ref "U$8") (pin "P$9") (pinfunction "P$9_P$9") (pintype "bidirectional"))
    )
    (net (code "176") (name "unconnected-(U$8-PadP$10)") (class "Default")
      (node (ref "U$8") (pin "P$10") (pinfunction "P$10_P$10") (pintype "bidirectional"))
    )
    (net (code "177") (name "unconnected-(U$8-PadP$11)") (class "Default")
      (node (ref "U$8") (pin "P$11") (pinfunction "P$11_P$11") (pintype "bidirectional"))
    )
    (net (code "178") (name "unconnected-(U$8-PadP$12)") (class "Default")
      (node (ref "U$8") (pin "P$12") (pinfunction "P$12_P$12") (pintype "bidirectional"))
    )
    (net (code "179") (name "unconnected-(U$8-PadP$13)") (class "Default")
      (node (ref "U$8") (pin "P$13") (pinfunction "P$13_P$13") (pintype "bidirectional"))
    )
    (net (code "180") (name "unconnected-(U$8-PadP$14)") (class "Default")
      (node (ref "U$8") (pin "P$14") (pinfunction "P$14_P$14") (pintype "bidirectional"))
    )
    (net (code "181") (name "unconnected-(U$8-PadP$15)") (class "Default")
      (node (ref "U$8") (pin "P$15") (pinfunction "P$15_P$15") (pintype "bidirectional"))
    )
    (net (code "182") (name "unconnected-(U$8-PadP$16)") (class "Default")
      (node (ref "U$8") (pin "P$16") (pinfunction "P$16_P$16") (pintype "bidirectional"))
    )
    (net (code "183") (name "unconnected-(U$10-PadP$7)") (class "Default")
      (node (ref "U$10") (pin "P$7") (pinfunction "P$7_P$7") (pintype "bidirectional"))
    )
    (net (code "184") (name "unconnected-(U$10-PadP$8)") (class "Default")
      (node (ref "U$10") (pin "P$8") (pinfunction "P$8_P$8") (pintype "bidirectional"))
    )
    (net (code "185") (name "unconnected-(U$10-PadP$9)") (class "Default")
      (node (ref "U$10") (pin "P$9") (pinfunction "P$9_P$9") (pintype "bidirectional"))
    )
    (net (code "186") (name "unconnected-(U$10-PadP$10)") (class "Default")
      (node (ref "U$10") (pin "P$10") (pinfunction "P$10_P$10") (pintype "bidirectional"))
    )
    (net (code "187") (name "unconnected-(U$11-PadP$7)") (class "Default")
      (node (ref "U$11") (pin "P$7") (pinfunction "P$7_P$7") (pintype "bidirectional"))
    )
    (net (code "188") (name "unconnected-(U$11-PadP$8)") (class "Default")
      (node (ref "U$11") (pin "P$8") (pinfunction "P$8_P$8") (pintype "bidirectional"))
    )
    (net (code "189") (name "unconnected-(U$11-PadP$9)") (class "Default")
      (node (ref "U$11") (pin "P$9") (pinfunction "P$9_P$9") (pintype "bidirectional"))
    )
    (net (code "190") (name "unconnected-(U$11-PadP$10)") (class "Default")
      (node (ref "U$11") (pin "P$10") (pinfunction "P$10_P$10") (pintype "bidirectional"))
    )
    (net (code "191") (name "unconnected-(U2-2IN+-Pad5)") (class "Default")
      (node (ref "U2") (pin "5") (pinfunction "2IN+_5") (pintype "input"))
    )
    (net (code "192") (name "unconnected-(U2-2IN--Pad6)") (class "Default")
      (node (ref "U2") (pin "6") (pinfunction "2IN-_6") (pintype "input"))
    )
    (net (code "193") (name "unconnected-(U2-2OUT-Pad7)") (class "Default")
      (node (ref "U2") (pin "7") (pinfunction "2OUT_7") (pintype "output"))
    )
  )
)
